# 33333.net
KiCad netlist of a schematic drawn in EasyEDA Pro
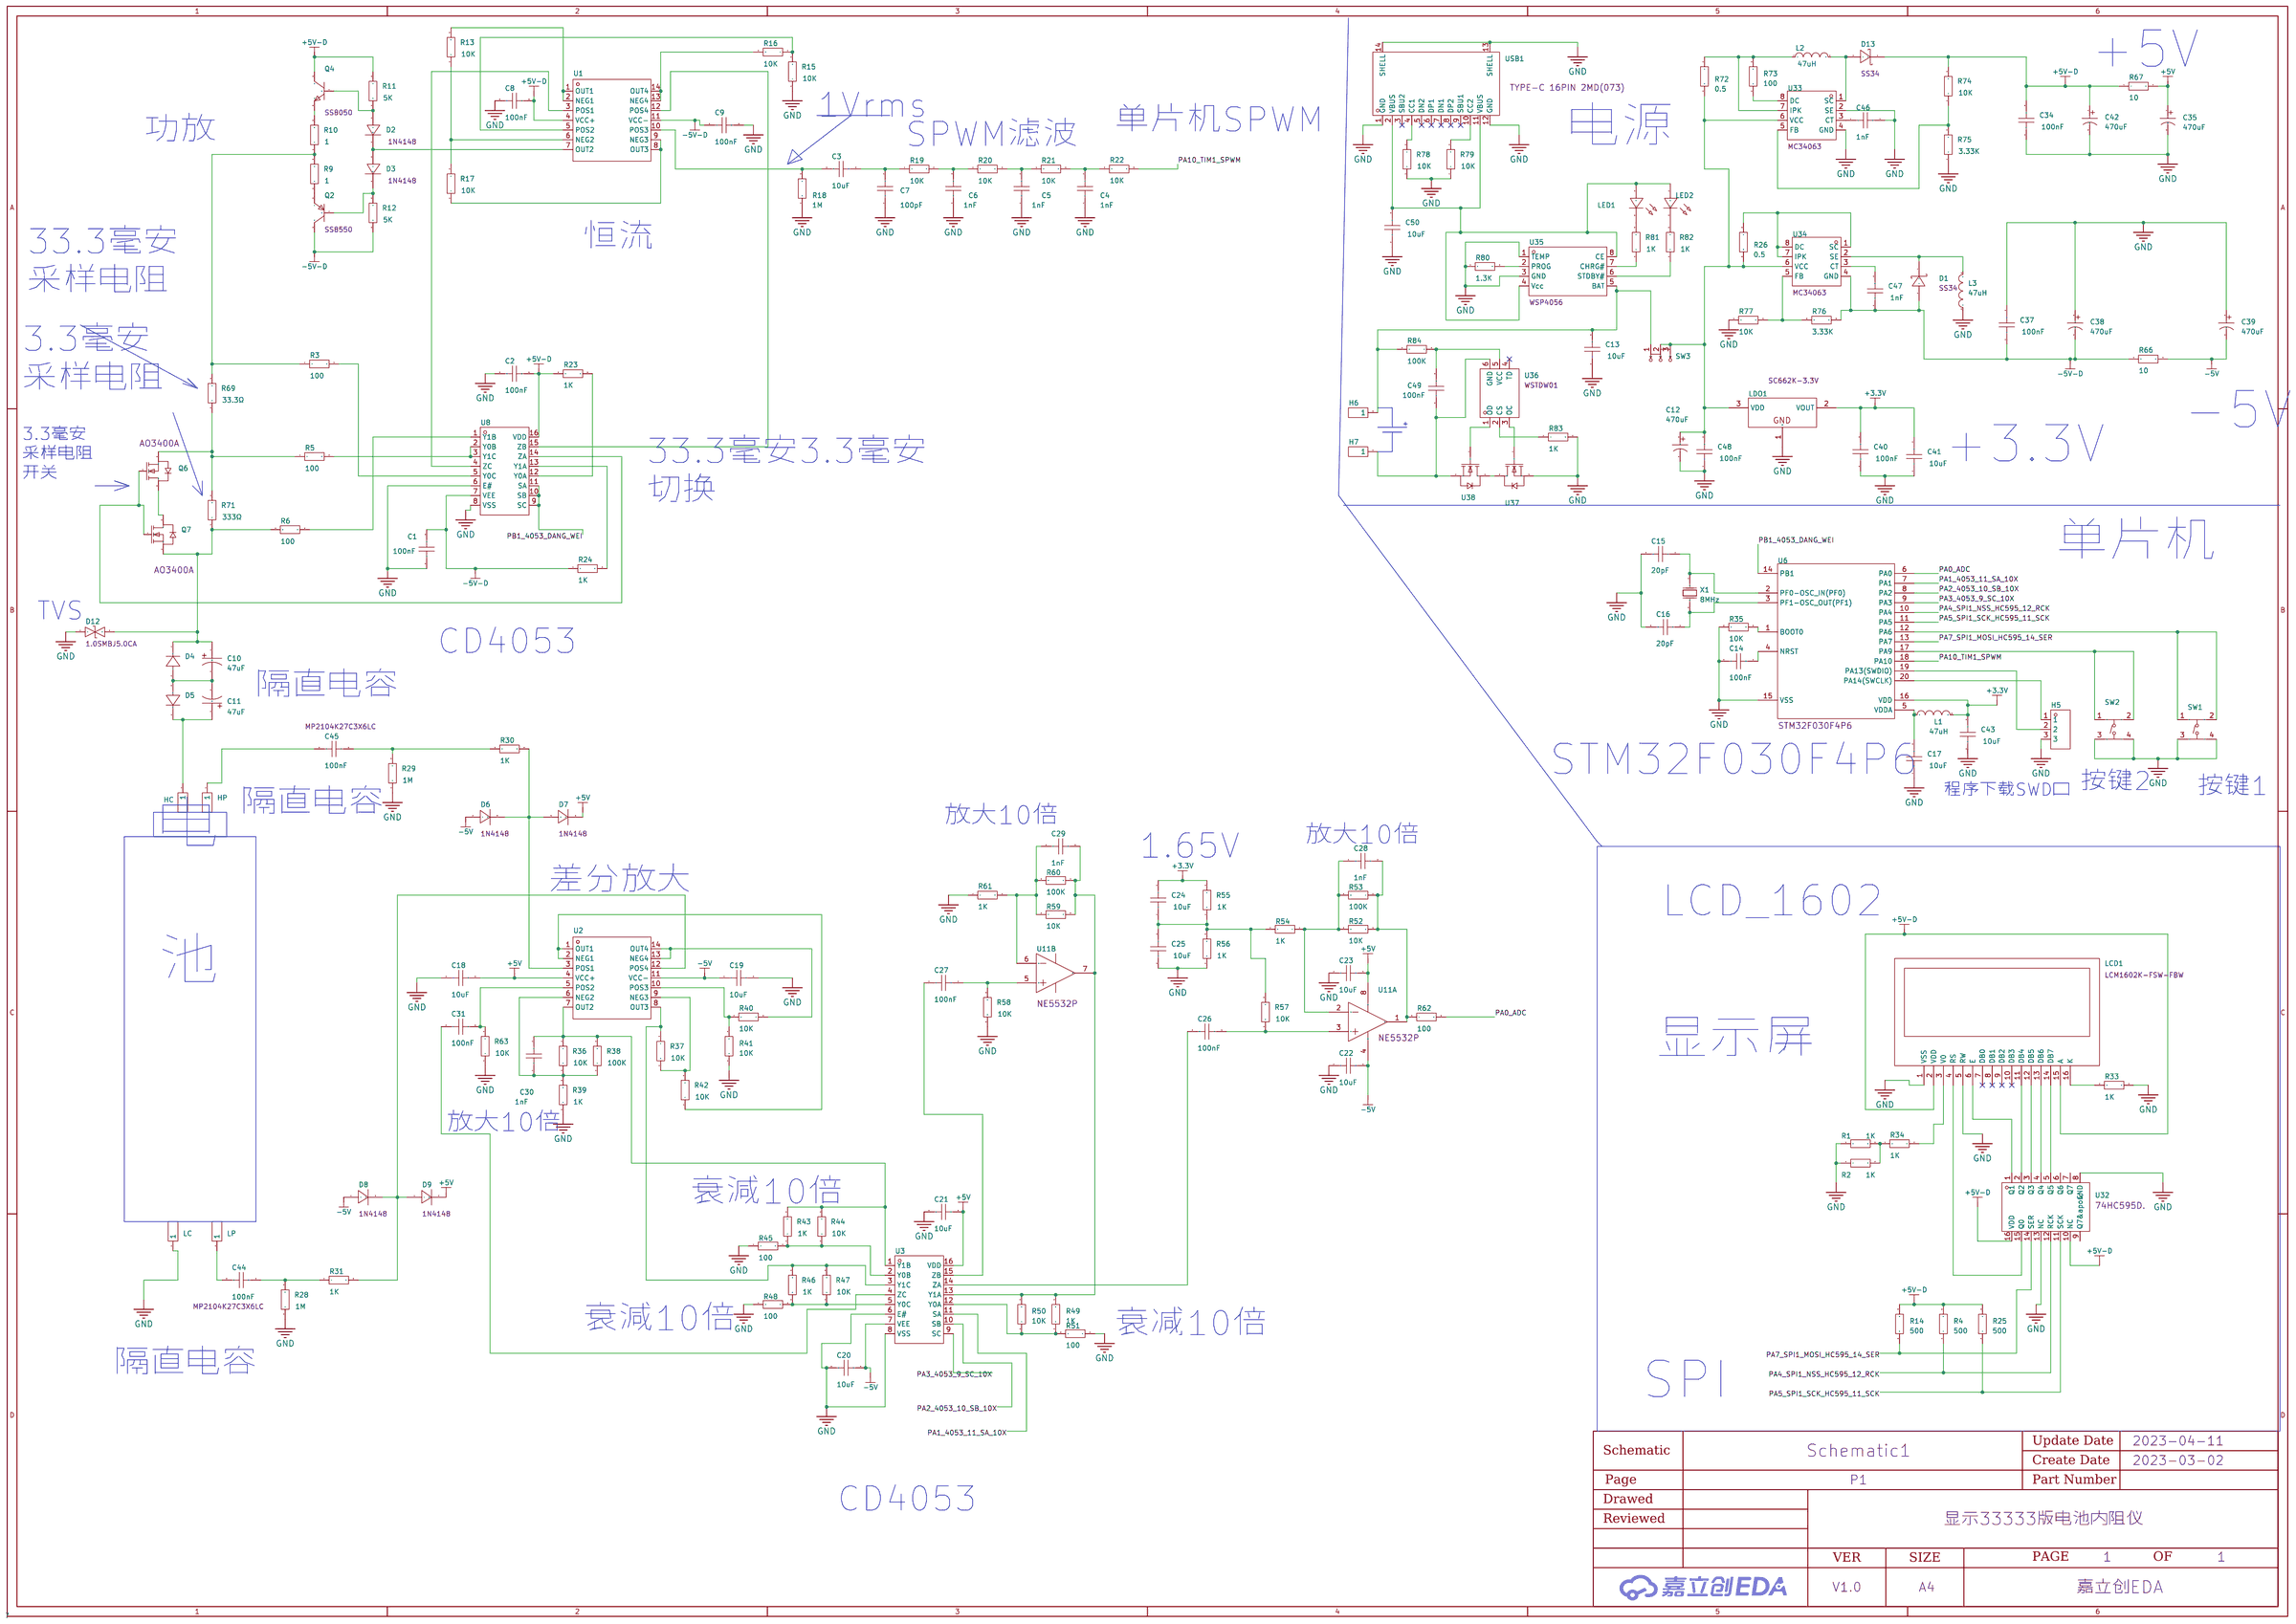
[diagram p0: schematic sheet]

(export (version "E")
  (design (tool "Eeschema 10.0.6"))
  (components
    (comp (ref "C1")
      (value "100nF")
      (footprint "easyedapro:C0603")
      (libsource (lib "easyedapro") (part "CapAcitance"))
    )
    (comp (ref "C2")
      (value "100nF")
      (footprint "easyedapro:C0603")
      (libsource (lib "easyedapro") (part "CapAcitance"))
    )
    (comp (ref "C3")
      (value "10uF")
      (footprint "easyedapro:C0603")
      (libsource (lib "easyedapro") (part "CapAcitance"))
    )
    (comp (ref "C4")
      (value "1nF")
      (footprint "easyedapro:C0603")
      (libsource (lib "easyedapro") (part "CapAcitance"))
    )
    (comp (ref "C5")
      (value "1nF")
      (footprint "easyedapro:C0603")
      (libsource (lib "easyedapro") (part "CapAcitance"))
    )
    (comp (ref "C6")
      (value "1nF")
      (footprint "easyedapro:C0603")
      (libsource (lib "easyedapro") (part "CapAcitance"))
    )
    (comp (ref "C7")
      (value "100pF")
      (footprint "easyedapro:C0603")
      (libsource (lib "easyedapro") (part "CapAcitance"))
    )
    (comp (ref "C8")
      (value "100nF")
      (footprint "easyedapro:C0603")
      (libsource (lib "easyedapro") (part "CapAcitance"))
    )
    (comp (ref "C9")
      (value "100nF")
      (footprint "easyedapro:C0603")
      (libsource (lib "easyedapro") (part "CapAcitance"))
    )
    (comp (ref "C10")
      (value "47uF")
      (footprint "easyedapro:CAP-TH_BD10.0-P5.00-D1.0-FD")
      (description "容值:47uF;精度:±20%;额定电压:200V;电容体直径:10mm;电容体长度:20mm;脚间距:5mm;工作寿命:5000hrs@105℃;")
      (fields (field (name "Manufacturer Part") "KF470M200G200A") (field (name "Manufacturer") "CapXon(丰宾)"))
      (libsource (lib "easyedapro") (part "KF470M200G200A"))
    )
    (comp (ref "C11")
      (value "47uF")
      (footprint "easyedapro:CAP-TH_BD10.0-P5.00-D1.0-FD")
      (description "容值:47uF;精度:±20%;额定电压:200V;电容体直径:10mm;电容体长度:20mm;脚间距:5mm;工作寿命:5000hrs@105℃;")
      (fields (field (name "Manufacturer Part") "KF470M200G200A") (field (name "Manufacturer") "CapXon(丰宾)"))
      (libsource (lib "easyedapro") (part "KF470M200G200A"))
    )
    (comp (ref "C12")
      (value "470uF")
      (footprint "easyedapro:CAP-TH_BD8.0-P3.50-D0.6-FD")
      (description "容值:470uF;精度:±20%;额定电压:16V;电容体直径:8mm;电容体长度:12mm;脚间距:3.5mm;工作寿命:2000hrs@105℃;")
      (fields
        (field (name "Manufacturer Part") "KM477M016F12RR0VH2FP0")
        (field (name "Manufacturer") "CX(承兴)")
      )
      (libsource (lib "easyedapro") (part "470uf16v"))
    )
    (comp (ref "C13")
      (value "10uF")
      (footprint "easyedapro:C0603")
      (libsource (lib "easyedapro") (part "CapAcitance"))
    )
    (comp (ref "C14")
      (value "100nF")
      (footprint "easyedapro:C0603")
      (libsource (lib "easyedapro") (part "CapAcitance"))
    )
    (comp (ref "C15")
      (value "20pF")
      (footprint "easyedapro:C0603")
      (libsource (lib "easyedapro") (part "CapAcitance"))
    )
    (comp (ref "C16")
      (value "20pF")
      (footprint "easyedapro:C0603")
      (libsource (lib "easyedapro") (part "CapAcitance"))
    )
    (comp (ref "C17")
      (value "10uF")
      (footprint "easyedapro:C0603")
      (libsource (lib "easyedapro") (part "CapAcitance"))
    )
    (comp (ref "C18")
      (value "10uF")
      (footprint "easyedapro:C0603")
      (libsource (lib "easyedapro") (part "CapAcitance"))
    )
    (comp (ref "C19")
      (value "10uF")
      (footprint "easyedapro:C0603")
      (libsource (lib "easyedapro") (part "CapAcitance"))
    )
    (comp (ref "C20")
      (value "10uF")
      (footprint "easyedapro:C0603")
      (libsource (lib "easyedapro") (part "CapAcitance"))
    )
    (comp (ref "C21")
      (value "10uF")
      (footprint "easyedapro:C0603")
      (libsource (lib "easyedapro") (part "CapAcitance"))
    )
    (comp (ref "C22")
      (value "10uF")
      (footprint "easyedapro:C0603")
      (libsource (lib "easyedapro") (part "CapAcitance"))
    )
    (comp (ref "C23")
      (value "10uF")
      (footprint "easyedapro:C0603")
      (libsource (lib "easyedapro") (part "CapAcitance"))
    )
    (comp (ref "C24")
      (value "10uF")
      (footprint "easyedapro:C0603")
      (libsource (lib "easyedapro") (part "CapAcitance"))
    )
    (comp (ref "C25")
      (value "10uF")
      (footprint "easyedapro:C0603")
      (libsource (lib "easyedapro") (part "CapAcitance"))
    )
    (comp (ref "C26")
      (value "100nF")
      (footprint "easyedapro:C0603")
      (libsource (lib "easyedapro") (part "CapAcitance"))
    )
    (comp (ref "C27")
      (value "100nF")
      (footprint "easyedapro:C0603")
      (libsource (lib "easyedapro") (part "CapAcitance"))
    )
    (comp (ref "C28")
      (value "1nF")
      (footprint "easyedapro:C0603")
      (libsource (lib "easyedapro") (part "CapAcitance"))
    )
    (comp (ref "C29")
      (value "1nF")
      (footprint "easyedapro:C0603")
      (libsource (lib "easyedapro") (part "CapAcitance"))
    )
    (comp (ref "C30")
      (value "1nF")
      (footprint "easyedapro:C0603")
      (libsource (lib "easyedapro") (part "CapAcitance"))
    )
    (comp (ref "C31")
      (value "100nF")
      (footprint "easyedapro:C0603")
      (libsource (lib "easyedapro") (part "CapAcitance"))
    )
    (comp (ref "C34")
      (value "100nF")
      (footprint "easyedapro:C0603")
      (libsource (lib "easyedapro") (part "CapAcitance"))
    )
    (comp (ref "C35")
      (value "470uF")
      (footprint "easyedapro:CAP-TH_BD8.0-P3.50-D0.6-FD")
      (description "容值:470uF;精度:±20%;额定电压:16V;电容体直径:8mm;电容体长度:12mm;脚间距:3.5mm;工作寿命:2000hrs@105℃;")
      (fields
        (field (name "Manufacturer Part") "KM477M016F12RR0VH2FP0")
        (field (name "Manufacturer") "CX(承兴)")
      )
      (libsource (lib "easyedapro") (part "470uf16v"))
    )
    (comp (ref "C37")
      (value "100nF")
      (footprint "easyedapro:C0603")
      (libsource (lib "easyedapro") (part "CapAcitance"))
    )
    (comp (ref "C38")
      (value "470uF")
      (footprint "easyedapro:CAP-TH_BD8.0-P3.50-D0.6-FD")
      (description "容值:470uF;精度:±20%;额定电压:16V;电容体直径:8mm;电容体长度:12mm;脚间距:3.5mm;工作寿命:2000hrs@105℃;")
      (fields
        (field (name "Manufacturer Part") "KM477M016F12RR0VH2FP0")
        (field (name "Manufacturer") "CX(承兴)")
      )
      (libsource (lib "easyedapro") (part "470uf16v"))
    )
    (comp (ref "C39")
      (value "470uF")
      (footprint "easyedapro:CAP-TH_BD8.0-P3.50-D0.6-FD")
      (description "容值:470uF;精度:±20%;额定电压:16V;电容体直径:8mm;电容体长度:12mm;脚间距:3.5mm;工作寿命:2000hrs@105℃;")
      (fields
        (field (name "Manufacturer Part") "KM477M016F12RR0VH2FP0")
        (field (name "Manufacturer") "CX(承兴)")
      )
      (libsource (lib "easyedapro") (part "470uf16v"))
    )
    (comp (ref "C40")
      (value "100nF")
      (footprint "easyedapro:C0603")
      (libsource (lib "easyedapro") (part "CapAcitance"))
    )
    (comp (ref "C41")
      (value "10uF")
      (footprint "easyedapro:C0603")
      (libsource (lib "easyedapro") (part "CapAcitance"))
    )
    (comp (ref "C42")
      (value "470uF")
      (footprint "easyedapro:CAP-TH_BD8.0-P3.50-D0.6-FD")
      (description "容值:470uF;精度:±20%;额定电压:16V;电容体直径:8mm;电容体长度:12mm;脚间距:3.5mm;工作寿命:2000hrs@105℃;")
      (fields
        (field (name "Manufacturer Part") "KM477M016F12RR0VH2FP0")
        (field (name "Manufacturer") "CX(承兴)")
      )
      (libsource (lib "easyedapro") (part "470uf16v"))
    )
    (comp (ref "C43")
      (value "10uF")
      (footprint "easyedapro:C0603")
      (libsource (lib "easyedapro") (part "CapAcitance"))
    )
    (comp (ref "C44")
      (value "100nF")
      (footprint "easyedapro:CAP-TH_L13.0-W6.0-P10.00-D1.0")
      (description "等级:X2;容值:100nF;精度:±10%;")
      (fields (field (name "Manufacturer Part") "MP2104K27C3X6LC") (field (name "Manufacturer") "SRD(圣融达)"))
      (libsource (lib "easyedapro") (part "MP2104KGC3XLC"))
    )
    (comp (ref "C45")
      (value "100nF")
      (footprint "easyedapro:CAP-TH_L13.0-W6.0-P10.00-D1.0")
      (description "等级:X2;容值:100nF;精度:±10%;")
      (fields (field (name "Manufacturer Part") "MP2104K27C3X6LC") (field (name "Manufacturer") "SRD(圣融达)"))
      (libsource (lib "easyedapro") (part "MP2104KGC3XLC"))
    )
    (comp (ref "C46")
      (value "1nF")
      (footprint "easyedapro:C0603")
      (libsource (lib "easyedapro") (part "CapAcitance"))
    )
    (comp (ref "C47")
      (value "1nF")
      (footprint "easyedapro:C0603")
      (libsource (lib "easyedapro") (part "CapAcitance"))
    )
    (comp (ref "C48")
      (value "100nF")
      (footprint "easyedapro:C0603")
      (libsource (lib "easyedapro") (part "CapAcitance"))
    )
    (comp (ref "C49")
      (value "100nF")
      (footprint "easyedapro:C0603")
      (libsource (lib "easyedapro") (part "CapAcitance"))
    )
    (comp (ref "C50")
      (value "10uF")
      (footprint "easyedapro:C0603")
      (libsource (lib "easyedapro") (part "CapAcitance"))
    )
    (comp (ref "D1")
      (value "SS34")
      (footprint "easyedapro:SMA_L4.3-W2.6-LS5.2-RD")
      (description "二极管配置:独立式;直流反向耐压(Vr):40V;平均整流电流(Io):3A;正向压降(Vf):550mV@3A;反向电流(Ir):500uA@40V;")
      (fields (field (name "Manufacturer Part") "SS34") (field (name "Manufacturer") "MDD"))
      (libsource (lib "easyedapro") (part "SS34_C8678"))
    )
    (comp (ref "D2")
      (value "1N4148")
      (footprint "easyedapro:DO-35_BD2.0-L4.0-P8.00-D0.5-FD")
      (fields (field (name "Manufacturer Part") "1N4148") (field (name "Manufacturer") "ST(先科)"))
      (libsource (lib "easyedapro") (part "1N4148"))
    )
    (comp (ref "D3")
      (value "1N4148")
      (footprint "easyedapro:DO-35_BD2.0-L4.0-P8.00-D0.5-FD")
      (fields (field (name "Manufacturer Part") "1N4148") (field (name "Manufacturer") "ST(先科)"))
      (libsource (lib "easyedapro") (part "1N4148"))
    )
    (comp (ref "D4")
      (value "~")
      (footprint "easyedapro:DO_1N4007")
      (libsource (lib "easyedapro") (part "D_1N4007"))
    )
    (comp (ref "D5")
      (value "~")
      (footprint "easyedapro:DO_1N4007")
      (libsource (lib "easyedapro") (part "D_1N4007"))
    )
    (comp (ref "D6")
      (value "1N4148")
      (footprint "easyedapro:DO-35_BD2.0-L4.0-P8.00-D0.5-FD")
      (fields (field (name "Manufacturer Part") "1N4148") (field (name "Manufacturer") "ST(先科)"))
      (libsource (lib "easyedapro") (part "1N4148"))
    )
    (comp (ref "D7")
      (value "1N4148")
      (footprint "easyedapro:DO-35_BD2.0-L4.0-P8.00-D0.5-FD")
      (fields (field (name "Manufacturer Part") "1N4148") (field (name "Manufacturer") "ST(先科)"))
      (libsource (lib "easyedapro") (part "1N4148"))
    )
    (comp (ref "D8")
      (value "1N4148")
      (footprint "easyedapro:DO-35_BD2.0-L4.0-P8.00-D0.5-FD")
      (fields (field (name "Manufacturer Part") "1N4148") (field (name "Manufacturer") "ST(先科)"))
      (libsource (lib "easyedapro") (part "1N4148"))
    )
    (comp (ref "D9")
      (value "1N4148")
      (footprint "easyedapro:DO-35_BD2.0-L4.0-P8.00-D0.5-FD")
      (fields (field (name "Manufacturer Part") "1N4148") (field (name "Manufacturer") "ST(先科)"))
      (libsource (lib "easyedapro") (part "1N4148"))
    )
    (comp (ref "D12")
      (value "1.0SMBJ5.0CA")
      (footprint "easyedapro:SMB_L4.6-W3.6-LS5.3-BI")
      (description "极性:双向;反向截止电压(Vrwm):5V;击穿电压:6.4V;峰值脉冲电流(Ipp)@10/1000s:108.7A;最大钳位电压:9.2V;")
      (fields (field (name "Manufacturer Part") "1.0SMBJ5.0CA") (field (name "Manufacturer") "BORN(伯恩半导体)"))
      (libsource (lib "easyedapro") (part "1.0SMBJ5.0CA"))
    )
    (comp (ref "D13")
      (value "SS34")
      (footprint "easyedapro:SMA_L4.3-W2.6-LS5.2-RD")
      (description "二极管配置:独立式;直流反向耐压(Vr):40V;平均整流电流(Io):3A;正向压降(Vf):550mV@3A;反向电流(Ir):500uA@40V;")
      (fields (field (name "Manufacturer Part") "SS34") (field (name "Manufacturer") "MDD"))
      (libsource (lib "easyedapro") (part "SS34_C8678"))
    )
    (comp (ref "H5")
      (value "~")
      (footprint "easyedapro:HDR-TH_3P-P2.54-V-M")
      (libsource (lib "easyedapro") (part "PZ254V-11-03P_C2937625"))
    )
    (comp (ref "H6")
      (value "~")
      (footprint "easyedapro:HDR-TH_1P-V-M_XKB_X4611WV-01I-C28D40")
      (libsource (lib "easyedapro") (part "HDR_1x1"))
    )
    (comp (ref "H7")
      (value "~")
      (footprint "easyedapro:HDR-TH_1P-V-M_XKB_X4611WV-01I-C28D40")
      (libsource (lib "easyedapro") (part "HDR_1x1"))
    )
    (comp (ref "HC")
      (value "~")
      (footprint "easyedapro:HDR-TH_1P-V-M_XKB_X4611WV-01I-C28D40")
      (libsource (lib "easyedapro") (part "HDR_1x1"))
    )
    (comp (ref "HP")
      (value "~")
      (footprint "easyedapro:HDR-TH_1P-V-M_XKB_X4611WV-01I-C28D40")
      (libsource (lib "easyedapro") (part "HDR_1x1"))
    )
    (comp (ref "L1")
      (value "47uH")
      (footprint "easyedapro:IND-SMD_L4.5-W4.0_SLF0403")
      (description "电感值:47uH;直流电阻(DCR):844mΩ;精度:±10%;额定电流:540mA;")
      (fields
        (field (name "Manufacturer Part") "SLF0403-470KTT")
        (field (name "Manufacturer") "Sunltech(韩国顺磁)")
      )
      (libsource (lib "easyedapro") (part "SLF0403-470KTT"))
    )
    (comp (ref "L2")
      (value "47uH")
      (footprint "easyedapro:IND-SMD_L4.5-W4.0_SLF0403")
      (description "电感值:47uH;直流电阻(DCR):844mΩ;精度:±10%;额定电流:540mA;")
      (fields
        (field (name "Manufacturer Part") "SLF0403-470KTT")
        (field (name "Manufacturer") "Sunltech(韩国顺磁)")
      )
      (libsource (lib "easyedapro") (part "SLF0403-470KTT"))
    )
    (comp (ref "L3")
      (value "47uH")
      (footprint "easyedapro:IND-SMD_L4.5-W4.0_SLF0403")
      (description "电感值:47uH;直流电阻(DCR):844mΩ;精度:±10%;额定电流:540mA;")
      (fields
        (field (name "Manufacturer Part") "SLF0403-470KTT")
        (field (name "Manufacturer") "Sunltech(韩国顺磁)")
      )
      (libsource (lib "easyedapro") (part "SLF0403-470KTT"))
    )
    (comp (ref "LC")
      (value "~")
      (footprint "easyedapro:HDR-TH_1P-V-M_XKB_X4611WV-01I-C28D40")
      (libsource (lib "easyedapro") (part "HDR_1x1"))
    )
    (comp (ref "LCD1")
      (value "LCM1602K-FSW-FBW")
      (footprint "easyedapro:MODULE-TH_LCM1602K")
      (description "尺寸(inch):-;主控芯片:KS0066U;")
      (fields
        (field (name "Manufacturer Part") "LCM1602K-FSW-FBW")
        (field (name "Manufacturer") "LONTECH(厦门龙特)")
      )
      (libsource (lib "easyedapro") (part "LCM1602K-FSW-FBW"))
    )
    (comp (ref "LDO1")
      (value "SC662K-3.3V")
      (footprint "easyedapro:SOT-23-3_L2.9-W1.3-P1.90-LS2.4-BR")
      (description "输出类型:固定;输出极性:正;最大输入电压:6V;输出电压:3.3V;输出电流:250mA;电源纹波抑制比(PSRR):50dB@(1kHz);")
      (fields (field (name "Manufacturer Part") "SC662K-3.3V") (field (name "Manufacturer") "FM(富满)"))
      (libsource (lib "easyedapro") (part "SC662K-3.3V"))
    )
    (comp (ref "LED1")
      (value "~")
      (footprint "easyedapro:LED_TH-3mm")
      (libsource (lib "easyedapro") (part "LED_TH-R"))
    )
    (comp (ref "LED2")
      (value "~")
      (footprint "easyedapro:LED_TH-3mm")
      (libsource (lib "easyedapro") (part "LED_TH-R"))
    )
    (comp (ref "LP")
      (value "~")
      (footprint "easyedapro:HDR-TH_1P-V-M_XKB_X4611WV-01I-C28D40")
      (libsource (lib "easyedapro") (part "HDR_1x1"))
    )
    (comp (ref "Q2")
      (value "SS8550")
      (footprint "easyedapro:SOT-23-3_L2.9-W1.6-P1.90-LS2.8-BR")
      (fields (field (name "Manufacturer Part") "SS8550") (field (name "Manufacturer") "ElecSuper(静芯微）"))
      (libsource (lib "easyedapro") (part "SS8550_C5249677"))
    )
    (comp (ref "Q4")
      (value "SS8050")
      (footprint "easyedapro:SOT-23-3_L2.9-W1.6-P1.90-LS2.8-BR")
      (fields (field (name "Manufacturer Part") "SS8050") (field (name "Manufacturer") "ElecSuper(静芯微）"))
      (libsource (lib "easyedapro") (part "SS8050_C5249676"))
    )
    (comp (ref "Q6")
      (value "AO3400A")
      (footprint "easyedapro:SOT-23-3_L2.9-W1.3-P1.90-LS2.4-BR")
      (fields (field (name "Manufacturer Part") "AO3400A") (field (name "Manufacturer") "UMW(广东友台半导体)"))
      (libsource (lib "easyedapro") (part "AO3400A_C347475"))
    )
    (comp (ref "Q7")
      (value "AO3400A")
      (footprint "easyedapro:SOT-23-3_L2.9-W1.3-P1.90-LS2.4-BR")
      (fields (field (name "Manufacturer Part") "AO3400A") (field (name "Manufacturer") "UMW(广东友台半导体)"))
      (libsource (lib "easyedapro") (part "AO3400A_C347475"))
    )
    (comp (ref "R1")
      (value "1K")
      (footprint "easyedapro:Res_1/8W")
      (libsource (lib "easyedapro") (part "电阻"))
    )
    (comp (ref "R2")
      (value "1K")
      (footprint "easyedapro:Res_1/8W")
      (libsource (lib "easyedapro") (part "电阻"))
    )
    (comp (ref "R3")
      (value "100")
      (footprint "easyedapro:Res_1/8W")
      (libsource (lib "easyedapro") (part "电阻"))
    )
    (comp (ref "R4")
      (value "500")
      (footprint "easyedapro:Res_1/8W")
      (libsource (lib "easyedapro") (part "电阻"))
    )
    (comp (ref "R5")
      (value "100")
      (footprint "easyedapro:Res_1/8W")
      (libsource (lib "easyedapro") (part "电阻"))
    )
    (comp (ref "R6")
      (value "100")
      (footprint "easyedapro:Res_1/8W")
      (libsource (lib "easyedapro") (part "电阻"))
    )
    (comp (ref "R9") (value "1") (footprint "easyedapro:Res_1/8W") (libsource (lib "easyedapro") (part "电阻")))
    (comp (ref "R10")
      (value "1")
      (footprint "easyedapro:Res_1/8W")
      (libsource (lib "easyedapro") (part "电阻"))
    )
    (comp (ref "R11")
      (value "5K")
      (footprint "easyedapro:Res_1/8W")
      (libsource (lib "easyedapro") (part "电阻"))
    )
    (comp (ref "R12")
      (value "5K")
      (footprint "easyedapro:Res_1/8W")
      (libsource (lib "easyedapro") (part "电阻"))
    )
    (comp (ref "R13")
      (value "10K")
      (footprint "easyedapro:Res_1/8W")
      (libsource (lib "easyedapro") (part "电阻"))
    )
    (comp (ref "R14")
      (value "500")
      (footprint "easyedapro:Res_1/8W")
      (libsource (lib "easyedapro") (part "电阻"))
    )
    (comp (ref "R15")
      (value "10K")
      (footprint "easyedapro:Res_1/8W")
      (libsource (lib "easyedapro") (part "电阻"))
    )
    (comp (ref "R16")
      (value "10K")
      (footprint "easyedapro:Res_1/8W")
      (libsource (lib "easyedapro") (part "电阻"))
    )
    (comp (ref "R17")
      (value "10K")
      (footprint "easyedapro:Res_1/8W")
      (libsource (lib "easyedapro") (part "电阻"))
    )
    (comp (ref "R18")
      (value "1M")
      (footprint "easyedapro:Res_1/8W")
      (libsource (lib "easyedapro") (part "电阻"))
    )
    (comp (ref "R19")
      (value "10K")
      (footprint "easyedapro:Res_1/8W")
      (libsource (lib "easyedapro") (part "电阻"))
    )
    (comp (ref "R20")
      (value "10K")
      (footprint "easyedapro:Res_1/8W")
      (libsource (lib "easyedapro") (part "电阻"))
    )
    (comp (ref "R21")
      (value "10K")
      (footprint "easyedapro:Res_1/8W")
      (libsource (lib "easyedapro") (part "电阻"))
    )
    (comp (ref "R22")
      (value "10K")
      (footprint "easyedapro:Res_1/8W")
      (libsource (lib "easyedapro") (part "电阻"))
    )
    (comp (ref "R23")
      (value "1K")
      (footprint "easyedapro:Res_1/8W")
      (libsource (lib "easyedapro") (part "电阻"))
    )
    (comp (ref "R24")
      (value "1K")
      (footprint "easyedapro:Res_1/8W")
      (libsource (lib "easyedapro") (part "电阻"))
    )
    (comp (ref "R25")
      (value "500")
      (footprint "easyedapro:Res_1/8W")
      (libsource (lib "easyedapro") (part "电阻"))
    )
    (comp (ref "R26") (value "0.5") (footprint "easyedapro:R0603") (libsource (lib "easyedapro") (part "电阻")))
    (comp (ref "R28")
      (value "1M")
      (footprint "easyedapro:Res_1/8W")
      (libsource (lib "easyedapro") (part "电阻"))
    )
    (comp (ref "R29")
      (value "1M")
      (footprint "easyedapro:Res_1/8W")
      (libsource (lib "easyedapro") (part "电阻"))
    )
    (comp (ref "R30")
      (value "1K")
      (footprint "easyedapro:Res_1/8W")
      (libsource (lib "easyedapro") (part "电阻"))
    )
    (comp (ref "R31")
      (value "1K")
      (footprint "easyedapro:Res_1/8W")
      (libsource (lib "easyedapro") (part "电阻"))
    )
    (comp (ref "R33")
      (value "1K")
      (footprint "easyedapro:Res_1/8W")
      (libsource (lib "easyedapro") (part "电阻"))
    )
    (comp (ref "R34")
      (value "1K")
      (footprint "easyedapro:Res_1/8W")
      (libsource (lib "easyedapro") (part "电阻"))
    )
    (comp (ref "R35")
      (value "10K")
      (footprint "easyedapro:Res_1/8W")
      (libsource (lib "easyedapro") (part "电阻"))
    )
    (comp (ref "R36")
      (value "10K")
      (footprint "easyedapro:Res_1/8W")
      (libsource (lib "easyedapro") (part "电阻"))
    )
    (comp (ref "R37")
      (value "10K")
      (footprint "easyedapro:Res_1/8W")
      (libsource (lib "easyedapro") (part "电阻"))
    )
    (comp (ref "R38")
      (value "100K")
      (footprint "easyedapro:Res_1/8W")
      (libsource (lib "easyedapro") (part "电阻"))
    )
    (comp (ref "R39")
      (value "1K")
      (footprint "easyedapro:Res_1/8W")
      (libsource (lib "easyedapro") (part "电阻"))
    )
    (comp (ref "R40")
      (value "10K")
      (footprint "easyedapro:Res_1/8W")
      (libsource (lib "easyedapro") (part "电阻"))
    )
    (comp (ref "R41")
      (value "10K")
      (footprint "easyedapro:Res_1/8W")
      (libsource (lib "easyedapro") (part "电阻"))
    )
    (comp (ref "R42")
      (value "10K")
      (footprint "easyedapro:Res_1/8W")
      (libsource (lib "easyedapro") (part "电阻"))
    )
    (comp (ref "R43")
      (value "1K")
      (footprint "easyedapro:Res_1/8W")
      (libsource (lib "easyedapro") (part "电阻"))
    )
    (comp (ref "R44")
      (value "10K")
      (footprint "easyedapro:Res_1/8W")
      (libsource (lib "easyedapro") (part "电阻"))
    )
    (comp (ref "R45")
      (value "100")
      (footprint "easyedapro:Res_1/8W")
      (libsource (lib "easyedapro") (part "电阻"))
    )
    (comp (ref "R46")
      (value "1K")
      (footprint "easyedapro:Res_1/8W")
      (libsource (lib "easyedapro") (part "电阻"))
    )
    (comp (ref "R47")
      (value "10K")
      (footprint "easyedapro:Res_1/8W")
      (libsource (lib "easyedapro") (part "电阻"))
    )
    (comp (ref "R48")
      (value "100")
      (footprint "easyedapro:Res_1/8W")
      (libsource (lib "easyedapro") (part "电阻"))
    )
    (comp (ref "R49")
      (value "1K")
      (footprint "easyedapro:Res_1/8W")
      (libsource (lib "easyedapro") (part "电阻"))
    )
    (comp (ref "R50")
      (value "10K")
      (footprint "easyedapro:Res_1/8W")
      (libsource (lib "easyedapro") (part "电阻"))
    )
    (comp (ref "R51")
      (value "100")
      (footprint "easyedapro:Res_1/8W")
      (libsource (lib "easyedapro") (part "电阻"))
    )
    (comp (ref "R52")
      (value "10K")
      (footprint "easyedapro:Res_1/8W")
      (libsource (lib "easyedapro") (part "电阻"))
    )
    (comp (ref "R53")
      (value "100K")
      (footprint "easyedapro:Res_1/8W")
      (libsource (lib "easyedapro") (part "电阻"))
    )
    (comp (ref "R54")
      (value "1K")
      (footprint "easyedapro:Res_1/8W")
      (libsource (lib "easyedapro") (part "电阻"))
    )
    (comp (ref "R55")
      (value "1K")
      (footprint "easyedapro:Res_1/8W")
      (libsource (lib "easyedapro") (part "电阻"))
    )
    (comp (ref "R56")
      (value "1K")
      (footprint "easyedapro:Res_1/8W")
      (libsource (lib "easyedapro") (part "电阻"))
    )
    (comp (ref "R57")
      (value "10K")
      (footprint "easyedapro:Res_1/8W")
      (libsource (lib "easyedapro") (part "电阻"))
    )
    (comp (ref "R58")
      (value "10K")
      (footprint "easyedapro:Res_1/8W")
      (libsource (lib "easyedapro") (part "电阻"))
    )
    (comp (ref "R59")
      (value "10K")
      (footprint "easyedapro:Res_1/8W")
      (libsource (lib "easyedapro") (part "电阻"))
    )
    (comp (ref "R60")
      (value "100K")
      (footprint "easyedapro:Res_1/8W")
      (libsource (lib "easyedapro") (part "电阻"))
    )
    (comp (ref "R61")
      (value "1K")
      (footprint "easyedapro:Res_1/8W")
      (libsource (lib "easyedapro") (part "电阻"))
    )
    (comp (ref "R62")
      (value "100")
      (footprint "easyedapro:Res_1/8W")
      (libsource (lib "easyedapro") (part "电阻"))
    )
    (comp (ref "R63")
      (value "10K")
      (footprint "easyedapro:Res_1/8W")
      (libsource (lib "easyedapro") (part "电阻"))
    )
    (comp (ref "R66") (value "10") (footprint "easyedapro:R0603") (libsource (lib "easyedapro") (part "电阻")))
    (comp (ref "R67") (value "10") (footprint "easyedapro:R0603") (libsource (lib "easyedapro") (part "电阻")))
    (comp (ref "R69")
      (value "33.3Ω")
      (footprint "easyedapro:R2512")
      (description "电阻类型:厚膜电阻;阻值:10Ω;精度:±5%;功率:2W;温度系数:±200ppm/℃;最大工作电压:200V;工作温度范围:-55℃~+155℃;")
      (fields (field (name "Manufacturer Part") "RC2512JK-7W10RL") (field (name "Manufacturer") "YAGEO(国巨)"))
      (libsource (lib "easyedapro") (part "RC2512JK-7W10RL"))
    )
    (comp (ref "R71")
      (value "333Ω")
      (footprint "easyedapro:R0603")
      (description "电阻类型:厚膜电阻;阻值:100Ω;精度:±1%;功率:100mW;温度系数:±100ppm/℃;最大工作电压:75V;工作温度范围:-55℃~+155℃;")
      (fields (field (name "Manufacturer Part") "AC0603FR-07100RL") (field (name "Manufacturer") "YAGEO(国巨)"))
      (libsource (lib "easyedapro") (part "AC0603FR-07100RL"))
    )
    (comp (ref "R72") (value "0.5") (footprint "easyedapro:R0603") (libsource (lib "easyedapro") (part "电阻")))
    (comp (ref "R73") (value "100") (footprint "easyedapro:R0603") (libsource (lib "easyedapro") (part "电阻")))
    (comp (ref "R74") (value "10K") (footprint "easyedapro:R0603") (libsource (lib "easyedapro") (part "电阻")))
    (comp (ref "R75")
      (value "3.33K")
      (footprint "easyedapro:R0603")
      (libsource (lib "easyedapro") (part "电阻"))
    )
    (comp (ref "R76")
      (value "3.33K")
      (footprint "easyedapro:R0603")
      (libsource (lib "easyedapro") (part "电阻"))
    )
    (comp (ref "R77") (value "10K") (footprint "easyedapro:R0603") (libsource (lib "easyedapro") (part "电阻")))
    (comp (ref "R78") (value "10K") (footprint "easyedapro:R0603") (libsource (lib "easyedapro") (part "电阻")))
    (comp (ref "R79") (value "10K") (footprint "easyedapro:R0603") (libsource (lib "easyedapro") (part "电阻")))
    (comp (ref "R80")
      (value "1.3K")
      (footprint "easyedapro:R0603")
      (libsource (lib "easyedapro") (part "电阻"))
    )
    (comp (ref "R81") (value "1K") (footprint "easyedapro:R0603") (libsource (lib "easyedapro") (part "电阻")))
    (comp (ref "R82") (value "1K") (footprint "easyedapro:R0603") (libsource (lib "easyedapro") (part "电阻")))
    (comp (ref "R83") (value "1K") (footprint "easyedapro:R0603") (libsource (lib "easyedapro") (part "电阻")))
    (comp (ref "R84")
      (value "100K")
      (footprint "easyedapro:R0603")
      (libsource (lib "easyedapro") (part "电阻"))
    )
    (comp (ref "SW1")
      (value "1TS005A-2600-5001")
      (footprint "easyedapro:SW-TH_4P-L6.0-W6.0-P4.50-LS6.5")
      (fields (field (name "Manufacturer") "HYP(鸿源精密)"))
      (libsource (lib "easyedapro") (part "1TS005A-2600-5001"))
    )
    (comp (ref "SW2")
      (value "1TS005A-2600-5001")
      (footprint "easyedapro:SW-TH_4P-L6.0-W6.0-P4.50-LS6.5")
      (fields (field (name "Manufacturer") "HYP(鸿源精密)"))
      (libsource (lib "easyedapro") (part "1TS005A-2600-5001"))
    )
    (comp (ref "SW3")
      (value "SS-12F20-G070")
      (footprint "easyedapro:SW-TH_G-SWITCH_SS-12F20-G070")
      (fields (field (name "Manufacturer") "G-Switch(品赞)"))
      (libsource (lib "easyedapro") (part "SS-12F20-G070"))
    )
    (comp (ref "U1")
      (value "TL084CN")
      (footprint "easyedapro:DIP-14_L17.8-W10.2-P2.54-BL")
      (description "运放类型:J-FET;放大器组数:4;增益带宽积（GBP）:4MHz;压摆率（SR）:16 V/us;电源电压:6V ~ 36V, ±3V ~ 18V;各通道供电电流:1.4mA;")
      (fields (field (name "Manufacturer") "TI(德州仪器)"))
      (libsource (lib "easyedapro") (part "TL084CN_C54501"))
    )
    (comp (ref "U2")
      (value "TL084CN")
      (footprint "easyedapro:DIP-14_L17.8-W10.2-P2.54-BL")
      (description "运放类型:J-FET;放大器组数:4;增益带宽积（GBP）:4MHz;压摆率（SR）:16 V/us;电源电压:6V ~ 36V, ±3V ~ 18V;各通道供电电流:1.4mA;")
      (fields (field (name "Manufacturer") "TI(德州仪器)"))
      (libsource (lib "easyedapro") (part "TL084CN_C54501"))
    )
    (comp (ref "U3")
      (value "CD4053BM/TR")
      (footprint "easyedapro:SOP-16_L9.9-W3.9-P1.27-LS6.1-BL")
      (fields (field (name "Manufacturer") "HGSEMI(华冠)"))
      (libsource (lib "easyedapro") (part "CD4053BM/TR"))
    )
    (comp (ref "U6")
      (value "STM32F030F4P6")
      (footprint "easyedapro:TSSOP-20_L6.5-W4.4-P0.65-LS6.4-BL")
      (fields (field (name "Manufacturer Part") "STM32F030F4P6") (field (name "Manufacturer") "ST(意法半导体)"))
      (libsource (lib "easyedapro") (part "STM32F030F4P6"))
    )
    (comp (ref "U8")
      (value "CD4053BM/TR")
      (footprint "easyedapro:SOP-16_L9.9-W3.9-P1.27-LS6.1-BL")
      (fields (field (name "Manufacturer") "HGSEMI(华冠)"))
      (libsource (lib "easyedapro") (part "CD4053BM/TR"))
    )
    (comp (ref "U11")
      (value "NE5532P")
      (footprint "easyedapro:DIP-8_L9.4-W6.4-P2.54-LS9.1-BL")
      (description "运放类型:General Purpose;放大器组数:2;增益带宽积（GBP）:10MHz;压摆率（SR）:9 V/us;电源电压:±5V ~ 15V;各通道供电电流:8mA;")
      (fields (field (name "Manufacturer Part") "NE5532P") (field (name "Manufacturer") "TI(德州仪器)"))
      (libsource (lib "easyedapro") (part "NE5532P"))
    )
    (comp (ref "U32")
      (value "74HC595D.")
      (footprint "easyedapro:SOP-16_L9.9-W3.9-P1.27-LS6.0-BL")
      (fields (field (name "Manufacturer Part") "74HC595D.") (field (name "Manufacturer") "FM(富满)"))
      (libsource (lib "easyedapro") (part "74HC595D."))
    )
    (comp (ref "U33")
      (value "MC34063")
      (footprint "easyedapro:SOIC-8_L5.0-W4.0-P1.27-LS6.0-BL")
      (fields (field (name "Manufacturer Part") "MC34063") (field (name "Manufacturer") "HXY MOSFET(华轩阳电子)"))
      (libsource (lib "easyedapro") (part "MC34063_C5349988"))
    )
    (comp (ref "U34")
      (value "MC34063")
      (footprint "easyedapro:SOIC-8_L5.0-W4.0-P1.27-LS6.0-BL")
      (fields (field (name "Manufacturer Part") "MC34063") (field (name "Manufacturer") "HXY MOSFET(华轩阳电子)"))
      (libsource (lib "easyedapro") (part "MC34063_C5349988"))
    )
    (comp (ref "U35")
      (value "WSP4056")
      (footprint "easyedapro:SOP-8_L5.1-W3.9-P1.27-LS6.0-BL")
      (fields (field (name "Manufacturer Part") "WSP4056") (field (name "Manufacturer") "WINSOK(微硕)"))
      (libsource (lib "easyedapro") (part "WSP4056"))
    )
    (comp (ref "U36")
      (value "WSTDW01")
      (footprint "easyedapro:SOT-23-6_L2.9-W1.6-P0.95-LS2.8-BR")
      (description "充电电池的类型:-;电池单元组数:-;最大充电电流:-;充满的电池组电压:-;最大供应电压:-;")
      (fields (field (name "Manufacturer Part") "WSTDW01") (field (name "Manufacturer") "WINSOK(微硕)"))
      (libsource (lib "easyedapro") (part "WSTDW01"))
    )
    (comp (ref "U37")
      (value "AO3400A")
      (footprint "easyedapro:SOT-23-3_L3.0-W1.6-P1.90-LS2.8-BR")
      (fields (field (name "Manufacturer") "ElecSuper(静芯微）"))
      (libsource (lib "easyedapro") (part "AO3400A_C5224194"))
    )
    (comp (ref "U38")
      (value "AO3400A")
      (footprint "easyedapro:SOT-23-3_L3.0-W1.6-P1.90-LS2.8-BR")
      (fields (field (name "Manufacturer") "ElecSuper(静芯微）"))
      (libsource (lib "easyedapro") (part "AO3400A_C5224194"))
    )
    (comp (ref "USB1")
      (value "TYPE-C 16PIN 2MD(073)")
      (footprint "easyedapro:USB-C-SMD_TYPE-C-6PIN-2MD-073")
      (description "连接器类型:Type-C;标准:-;公母:母座;触点数量:16;端口数量:1;安装方式:卧贴;额定电流 - 电源:5A;工作温度范围:-25℃~+85℃;")
      (fields
        (field (name "Manufacturer Part") "TYPE-C 16PIN 2MD(073)")
        (field (name "Manufacturer") "SHOU HAN(首韩)")
      )
      (libsource (lib "easyedapro") (part "TYPE-C 16PIN 2MD(073)"))
    )
    (comp (ref "X1")
      (value "8MHz")
      (footprint "easyedapro:OSC-TH_L10.0-W4.5-P5.00")
      (description "晶振类型:49S晶振;频率:8MHz;频率公差:±20ppm;频率稳定度:±30ppm;负载电容:20pF;工作温度:-20℃~+70℃;")
      (fields (field (name "Manufacturer Part") "X49SD8MSD2SC") (field (name "Manufacturer") "YXC(扬兴晶振)"))
      (libsource (lib "easyedapro") (part "X49SD8MSD2SC"))
    )
  )
  (nets
    (net (code "1") (name "+3.3V") (class "Default")
      (node (ref "C24") (pin "2") (pinfunction "2_2") (pintype "input"))
      (node (ref "C40") (pin "2") (pinfunction "2_2") (pintype "input"))
      (node (ref "C41") (pin "2") (pinfunction "2_2") (pintype "input"))
      (node (ref "C43") (pin "2") (pinfunction "2_2") (pintype "input"))
      (node (ref "L1") (pin "2") (pinfunction "2_2") (pintype "input"))
      (node (ref "LDO1") (pin "2") (pinfunction "VOUT_2") (pintype "input"))
      (node (ref "R55") (pin "2") (pinfunction "2_2") (pintype "input"))
      (node (ref "U6") (pin "16") (pinfunction "VDD_16") (pintype "input"))
    )
    (net (code "2") (name "+5V") (class "Default")
      (node (ref "C18") (pin "2") (pinfunction "2_2") (pintype "input"))
      (node (ref "C21") (pin "2") (pinfunction "2_2") (pintype "input"))
      (node (ref "C23") (pin "2") (pinfunction "2_2") (pintype "input"))
      (node (ref "C35") (pin "1") (pinfunction "1_1") (pintype "input"))
      (node (ref "D7") (pin "2") (pinfunction "C_2") (pintype "input"))
      (node (ref "D9") (pin "2") (pinfunction "C_2") (pintype "input"))
      (node (ref "R67") (pin "2") (pinfunction "2_2") (pintype "input"))
      (node (ref "U11") (pin "8") (pinfunction "VCC+_8") (pintype "input"))
      (node (ref "U2") (pin "4") (pinfunction "VCC+_4") (pintype "input"))
      (node (ref "U3") (pin "16") (pinfunction "VDD_16") (pintype "input"))
    )
    (net (code "3") (name "+5V-D") (class "Default")
      (node (ref "C2") (pin "2") (pinfunction "2_2") (pintype "input"))
      (node (ref "C34") (pin "2") (pinfunction "2_2") (pintype "input"))
      (node (ref "C42") (pin "1") (pinfunction "1_1") (pintype "input"))
      (node (ref "C8") (pin "2") (pinfunction "2_2") (pintype "input"))
      (node (ref "D13") (pin "1") (pinfunction "K_1") (pintype "input"))
      (node (ref "LCD1") (pin "15") (pinfunction "A_15") (pintype "input"))
      (node (ref "LCD1") (pin "2") (pinfunction "VDD_2") (pintype "input"))
      (node (ref "Q4") (pin "3") (pinfunction "C_3") (pintype "input"))
      (node (ref "R11") (pin "2") (pinfunction "2_2") (pintype "input"))
      (node (ref "R14") (pin "2") (pinfunction "2_2") (pintype "input"))
      (node (ref "R23") (pin "1") (pinfunction "1_1") (pintype "input"))
      (node (ref "R25") (pin "2") (pinfunction "2_2") (pintype "input"))
      (node (ref "R4") (pin "2") (pinfunction "2_2") (pintype "input"))
      (node (ref "R67") (pin "1") (pinfunction "1_1") (pintype "input"))
      (node (ref "R74") (pin "2") (pinfunction "2_2") (pintype "input"))
      (node (ref "U1") (pin "4") (pinfunction "VCC+_4") (pintype "input"))
      (node (ref "U32") (pin "10") (pinfunction "NC_10") (pintype "input"))
      (node (ref "U32") (pin "16") (pinfunction "VDD_16") (pintype "input"))
      (node (ref "U8") (pin "16") (pinfunction "VDD_16") (pintype "input"))
    )
    (net (code "4") (name "-5V") (class "Default")
      (node (ref "C19") (pin "1") (pinfunction "1_1") (pintype "input"))
      (node (ref "C20") (pin "2") (pinfunction "2_2") (pintype "input"))
      (node (ref "C22") (pin "2") (pinfunction "2_2") (pintype "input"))
      (node (ref "C39") (pin "2") (pinfunction "2_2") (pintype "input"))
      (node (ref "D6") (pin "1") (pinfunction "A_1") (pintype "input"))
      (node (ref "D8") (pin "1") (pinfunction "A_1") (pintype "input"))
      (node (ref "R66") (pin "2") (pinfunction "2_2") (pintype "input"))
      (node (ref "U11") (pin "4") (pinfunction "VCC-_4") (pintype "input"))
      (node (ref "U2") (pin "11") (pinfunction "VCC-_11") (pintype "input"))
      (node (ref "U3") (pin "7") (pinfunction "VEE_7") (pintype "input"))
    )
    (net (code "5") (name "-5V-D") (class "Default")
      (node (ref "C1") (pin "2") (pinfunction "2_2") (pintype "input"))
      (node (ref "C37") (pin "1") (pinfunction "1_1") (pintype "input"))
      (node (ref "C38") (pin "2") (pinfunction "2_2") (pintype "input"))
      (node (ref "C47") (pin "1") (pinfunction "1_1") (pintype "input"))
      (node (ref "C9") (pin "1") (pinfunction "1_1") (pintype "input"))
      (node (ref "D1") (pin "2") (pinfunction "A_2") (pintype "input"))
      (node (ref "Q2") (pin "3") (pinfunction "C_3") (pintype "input"))
      (node (ref "R12") (pin "1") (pinfunction "1_1") (pintype "input"))
      (node (ref "R24") (pin "1") (pinfunction "1_1") (pintype "input"))
      (node (ref "R66") (pin "1") (pinfunction "1_1") (pintype "input"))
      (node (ref "R76") (pin "2") (pinfunction "2_2") (pintype "input"))
      (node (ref "U1") (pin "11") (pinfunction "VCC-_11") (pintype "input"))
      (node (ref "U34") (pin "4") (pinfunction "GND_4") (pintype "input"))
      (node (ref "U8") (pin "7") (pinfunction "VEE_7") (pintype "input"))
    )
    (net (code "6") (name "/PA0_ADC") (class "Default")
      (node (ref "R62") (pin "2") (pinfunction "2_2") (pintype "input"))
      (node (ref "U6") (pin "6") (pinfunction "PA0_6") (pintype "bidirectional"))
    )
    (net (code "7") (name "/PA1_4053_11_SA_10X") (class "Default")
      (node (ref "U3") (pin "11") (pinfunction "SA_11") (pintype "input"))
      (node (ref "U6") (pin "7") (pinfunction "PA1_7") (pintype "bidirectional"))
    )
    (net (code "8") (name "/PA2_4053_10_SB_10X") (class "Default")
      (node (ref "U3") (pin "10") (pinfunction "SB_10") (pintype "input"))
      (node (ref "U6") (pin "8") (pinfunction "PA2_8") (pintype "bidirectional"))
    )
    (net (code "9") (name "/PA3_4053_9_SC_10X") (class "Default")
      (node (ref "U3") (pin "9") (pinfunction "SC_9") (pintype "input"))
      (node (ref "U6") (pin "9") (pinfunction "PA3_9") (pintype "bidirectional"))
    )
    (net (code "10") (name "/PA4_SPI1_NSS_HC595_12_RCK") (class "Default")
      (node (ref "R4") (pin "1") (pinfunction "1_1") (pintype "input"))
      (node (ref "U32") (pin "12") (pinfunction "RCK_12") (pintype "input"))
      (node (ref "U6") (pin "10") (pinfunction "PA4_10") (pintype "bidirectional"))
    )
    (net (code "11") (name "/PA5_SPI1_SCK_HC595_11_SCK") (class "Default")
      (node (ref "R25") (pin "1") (pinfunction "1_1") (pintype "input"))
      (node (ref "U32") (pin "11") (pinfunction "SCK_11") (pintype "input"))
      (node (ref "U6") (pin "11") (pinfunction "PA5_11") (pintype "bidirectional"))
    )
    (net (code "12") (name "/PA7_SPI1_MOSI_HC595_14_SER") (class "Default")
      (node (ref "R14") (pin "1") (pinfunction "1_1") (pintype "input"))
      (node (ref "U32") (pin "14") (pinfunction "SER_14") (pintype "input"))
      (node (ref "U6") (pin "13") (pinfunction "PA7_13") (pintype "bidirectional"))
    )
    (net (code "13") (name "/PA10_TIM1_SPWM") (class "Default")
      (node (ref "R22") (pin "2") (pinfunction "2_2") (pintype "input"))
      (node (ref "U6") (pin "18") (pinfunction "PA10_18") (pintype "bidirectional"))
    )
    (net (code "14") (name "/PB1_4053_DANG_WEI") (class "Default")
      (node (ref "U6") (pin "14") (pinfunction "PB1_14") (pintype "bidirectional"))
      (node (ref "U8") (pin "10") (pinfunction "SB_10") (pintype "input"))
      (node (ref "U8") (pin "11") (pinfunction "SA_11") (pintype "input"))
      (node (ref "U8") (pin "9") (pinfunction "SC_9") (pintype "input"))
    )
    (net (code "15") (name "GND") (class "Default")
      (node (ref "C1") (pin "1") (pinfunction "1_1") (pintype "input"))
      (node (ref "C12") (pin "2") (pinfunction "2_2") (pintype "input"))
      (node (ref "C13") (pin "1") (pinfunction "1_1") (pintype "input"))
      (node (ref "C14") (pin "2") (pinfunction "2_2") (pintype "input"))
      (node (ref "C15") (pin "2") (pinfunction "2_2") (pintype "input"))
      (node (ref "C16") (pin "2") (pinfunction "2_2") (pintype "input"))
      (node (ref "C17") (pin "1") (pinfunction "1_1") (pintype "input"))
      (node (ref "C18") (pin "1") (pinfunction "1_1") (pintype "input"))
      (node (ref "C19") (pin "2") (pinfunction "2_2") (pintype "input"))
      (node (ref "C2") (pin "1") (pinfunction "1_1") (pintype "input"))
      (node (ref "C20") (pin "1") (pinfunction "1_1") (pintype "input"))
      (node (ref "C21") (pin "1") (pinfunction "1_1") (pintype "input"))
      (node (ref "C22") (pin "1") (pinfunction "1_1") (pintype "input"))
      (node (ref "C23") (pin "1") (pinfunction "1_1") (pintype "input"))
      (node (ref "C25") (pin "1") (pinfunction "1_1") (pintype "input"))
      (node (ref "C34") (pin "1") (pinfunction "1_1") (pintype "input"))
      (node (ref "C35") (pin "2") (pinfunction "2_2") (pintype "input"))
      (node (ref "C37") (pin "2") (pinfunction "2_2") (pintype "input"))
      (node (ref "C38") (pin "1") (pinfunction "1_1") (pintype "input"))
      (node (ref "C39") (pin "1") (pinfunction "1_1") (pintype "input"))
      (node (ref "C4") (pin "1") (pinfunction "1_1") (pintype "input"))
      (node (ref "C40") (pin "1") (pinfunction "1_1") (pintype "input"))
      (node (ref "C41") (pin "1") (pinfunction "1_1") (pintype "input"))
      (node (ref "C42") (pin "2") (pinfunction "2_2") (pintype "input"))
      (node (ref "C43") (pin "1") (pinfunction "1_1") (pintype "input"))
      (node (ref "C46") (pin "2") (pinfunction "2_2") (pintype "input"))
      (node (ref "C48") (pin "1") (pinfunction "1_1") (pintype "input"))
      (node (ref "C5") (pin "1") (pinfunction "1_1") (pintype "input"))
      (node (ref "C50") (pin "1") (pinfunction "1_1") (pintype "input"))
      (node (ref "C6") (pin "1") (pinfunction "1_1") (pintype "input"))
      (node (ref "C7") (pin "1") (pinfunction "1_1") (pintype "input"))
      (node (ref "C8") (pin "1") (pinfunction "1_1") (pintype "input"))
      (node (ref "C9") (pin "2") (pinfunction "2_2") (pintype "input"))
      (node (ref "D12") (pin "1") (pinfunction "1_1") (pintype "input"))
      (node (ref "H5") (pin "3") (pinfunction "3_3") (pintype "input"))
      (node (ref "L3") (pin "1") (pinfunction "1_1") (pintype "input"))
      (node (ref "LC") (pin "1") (pinfunction "1_1") (pintype "unspecified"))
      (node (ref "LCD1") (pin "1") (pinfunction "VSS_1") (pintype "input"))
      (node (ref "LCD1") (pin "5") (pinfunction "RW_5") (pintype "input"))
      (node (ref "LDO1") (pin "1") (pinfunction "GND_1") (pintype "input"))
      (node (ref "R1") (pin "1") (pinfunction "1_1") (pintype "input"))
      (node (ref "R15") (pin "1") (pinfunction "1_1") (pintype "input"))
      (node (ref "R18") (pin "1") (pinfunction "1_1") (pintype "input"))
      (node (ref "R2") (pin "1") (pinfunction "1_1") (pintype "input"))
      (node (ref "R28") (pin "1") (pinfunction "1_1") (pintype "input"))
      (node (ref "R29") (pin "1") (pinfunction "1_1") (pintype "input"))
      (node (ref "R33") (pin "2") (pinfunction "2_2") (pintype "input"))
      (node (ref "R35") (pin "2") (pinfunction "2_2") (pintype "input"))
      (node (ref "R39") (pin "1") (pinfunction "1_1") (pintype "input"))
      (node (ref "R41") (pin "1") (pinfunction "1_1") (pintype "input"))
      (node (ref "R45") (pin "1") (pinfunction "1_1") (pintype "input"))
      (node (ref "R48") (pin "1") (pinfunction "1_1") (pintype "input"))
      (node (ref "R51") (pin "1") (pinfunction "1_1") (pintype "input"))
      (node (ref "R56") (pin "1") (pinfunction "1_1") (pintype "input"))
      (node (ref "R58") (pin "1") (pinfunction "1_1") (pintype "input"))
      (node (ref "R61") (pin "1") (pinfunction "1_1") (pintype "input"))
      (node (ref "R63") (pin "1") (pinfunction "1_1") (pintype "input"))
      (node (ref "R75") (pin "1") (pinfunction "1_1") (pintype "input"))
      (node (ref "R77") (pin "1") (pinfunction "1_1") (pintype "input"))
      (node (ref "R78") (pin "1") (pinfunction "1_1") (pintype "input"))
      (node (ref "R79") (pin "1") (pinfunction "1_1") (pintype "input"))
      (node (ref "R80") (pin "1") (pinfunction "1_1") (pintype "input"))
      (node (ref "R83") (pin "2") (pinfunction "2_2") (pintype "input"))
      (node (ref "SW1") (pin "3") (pinfunction "3_3") (pintype "input"))
      (node (ref "SW1") (pin "4") (pinfunction "4_4") (pintype "input"))
      (node (ref "SW2") (pin "3") (pinfunction "3_3") (pintype "input"))
      (node (ref "SW2") (pin "4") (pinfunction "4_4") (pintype "input"))
      (node (ref "U3") (pin "6") (pinfunction "E#_6") (pintype "input"))
      (node (ref "U3") (pin "8") (pinfunction "VSS_8") (pintype "input"))
      (node (ref "U32") (pin "13") (pinfunction "NC_13") (pintype "input"))
      (node (ref "U32") (pin "8") (pinfunction "GND_8") (pintype "input"))
      (node (ref "U33") (pin "2") (pinfunction "SE_2") (pintype "input"))
      (node (ref "U33") (pin "4") (pinfunction "GND_4") (pintype "input"))
      (node (ref "U35") (pin "1") (pinfunction "TEMP_1") (pintype "input"))
      (node (ref "U35") (pin "3") (pinfunction "GND_3") (pintype "input"))
      (node (ref "U37") (pin "2") (pinfunction "S_2") (pintype "input"))
      (node (ref "U6") (pin "15") (pinfunction "VSS_15") (pintype "input"))
      (node (ref "U8") (pin "6") (pinfunction "E#_6") (pintype "input"))
      (node (ref "U8") (pin "8") (pinfunction "VSS_8") (pintype "input"))
      (node (ref "USB1") (pin "1") (pinfunction "GND_1") (pintype "input"))
      (node (ref "USB1") (pin "12") (pinfunction "GND_12") (pintype "input"))
      (node (ref "USB1") (pin "13") (pinfunction "SHELL_13") (pintype "input"))
      (node (ref "USB1") (pin "14") (pinfunction "SHELL_14") (pintype "input"))
    )
    (net (code "16") (name "Net-(C3-Pad2)") (class "Default")
      (node (ref "C3") (pin "2") (pinfunction "2_2") (pintype "input"))
      (node (ref "C7") (pin "2") (pinfunction "2_2") (pintype "input"))
      (node (ref "R19") (pin "1") (pinfunction "1_1") (pintype "input"))
    )
    (net (code "17") (name "Net-(C4-Pad2)") (class "Default")
      (node (ref "C4") (pin "2") (pinfunction "2_2") (pintype "input"))
      (node (ref "R21") (pin "2") (pinfunction "2_2") (pintype "input"))
      (node (ref "R22") (pin "1") (pinfunction "1_1") (pintype "input"))
    )
    (net (code "18") (name "Net-(C5-Pad2)") (class "Default")
      (node (ref "C5") (pin "2") (pinfunction "2_2") (pintype "input"))
      (node (ref "R20") (pin "2") (pinfunction "2_2") (pintype "input"))
      (node (ref "R21") (pin "1") (pinfunction "1_1") (pintype "input"))
    )
    (net (code "19") (name "Net-(C6-Pad2)") (class "Default")
      (node (ref "C6") (pin "2") (pinfunction "2_2") (pintype "input"))
      (node (ref "R19") (pin "2") (pinfunction "2_2") (pintype "input"))
      (node (ref "R20") (pin "1") (pinfunction "1_1") (pintype "input"))
    )
    (net (code "20") (name "Net-(C24-Pad1)") (class "Default")
      (node (ref "C24") (pin "1") (pinfunction "1_1") (pintype "input"))
      (node (ref "C25") (pin "2") (pinfunction "2_2") (pintype "input"))
      (node (ref "R54") (pin "2") (pinfunction "2_2") (pintype "input"))
      (node (ref "R55") (pin "1") (pinfunction "1_1") (pintype "input"))
      (node (ref "R56") (pin "2") (pinfunction "2_2") (pintype "input"))
      (node (ref "R57") (pin "2") (pinfunction "2_2") (pintype "input"))
    )
    (net (code "21") (name "Net-(C44-Pad1)") (class "Default")
      (node (ref "C44") (pin "1") (pinfunction "1_1") (pintype "input"))
      (node (ref "R28") (pin "2") (pinfunction "2_2") (pintype "input"))
      (node (ref "R31") (pin "1") (pinfunction "1_1") (pintype "input"))
    )
    (net (code "22") (name "Net-(C44-Pad2)") (class "Default")
      (node (ref "C44") (pin "2") (pinfunction "2_2") (pintype "input"))
      (node (ref "LP") (pin "1") (pinfunction "1_1") (pintype "unspecified"))
    )
    (net (code "23") (name "Net-(C45-Pad1)") (class "Default")
      (node (ref "C45") (pin "1") (pinfunction "1_1") (pintype "input"))
      (node (ref "R29") (pin "2") (pinfunction "2_2") (pintype "input"))
      (node (ref "R30") (pin "1") (pinfunction "1_1") (pintype "input"))
    )
    (net (code "24") (name "Net-(C45-Pad2)") (class "Default")
      (node (ref "C45") (pin "2") (pinfunction "2_2") (pintype "input"))
      (node (ref "HP") (pin "1") (pinfunction "1_1") (pintype "unspecified"))
    )
    (net (code "25") (name "Net-(D1-K)") (class "Default")
      (node (ref "D1") (pin "1") (pinfunction "K_1") (pintype "input"))
      (node (ref "L3") (pin "2") (pinfunction "2_2") (pintype "input"))
      (node (ref "U34") (pin "2") (pinfunction "SE_2") (pintype "input"))
    )
    (net (code "26") (name "Net-(D2-A)") (class "Default")
      (node (ref "D2") (pin "1") (pinfunction "A_1") (pintype "input"))
      (node (ref "Q4") (pin "1") (pinfunction "B_1") (pintype "input"))
      (node (ref "R11") (pin "1") (pinfunction "1_1") (pintype "input"))
    )
    (net (code "27") (name "Net-(D2-C)") (class "Default")
      (node (ref "D2") (pin "2") (pinfunction "C_2") (pintype "input"))
      (node (ref "D3") (pin "1") (pinfunction "A_1") (pintype "input"))
      (node (ref "U1") (pin "7") (pinfunction "OUT2_7") (pintype "input"))
    )
    (net (code "28") (name "Net-(D3-C)") (class "Default")
      (node (ref "D3") (pin "2") (pinfunction "C_2") (pintype "input"))
      (node (ref "Q2") (pin "1") (pinfunction "B_1") (pintype "input"))
      (node (ref "R12") (pin "2") (pinfunction "2_2") (pintype "input"))
    )
    (net (code "29") (name "Net-(D4-A)") (class "Default")
      (node (ref "C10") (pin "2") (pinfunction "2_2") (pintype "input"))
      (node (ref "C11") (pin "2") (pinfunction "2_2") (pintype "input"))
      (node (ref "D4") (pin "2") (pinfunction "A_2") (pintype "input"))
      (node (ref "D5") (pin "2") (pinfunction "A_2") (pintype "input"))
    )
    (net (code "30") (name "Net-(D4-K)") (class "Default")
      (node (ref "C10") (pin "1") (pinfunction "1_1") (pintype "input"))
      (node (ref "D12") (pin "2") (pinfunction "2_2") (pintype "input"))
      (node (ref "D4") (pin "1") (pinfunction "K_1") (pintype "input"))
      (node (ref "Q7") (pin "2") (pinfunction "S_2") (pintype "input"))
      (node (ref "R6") (pin "1") (pinfunction "1_1") (pintype "input"))
      (node (ref "R71") (pin "1") (pinfunction "1_1") (pintype "input"))
    )
    (net (code "31") (name "Net-(D5-K)") (class "Default")
      (node (ref "C11") (pin "1") (pinfunction "1_1") (pintype "input"))
      (node (ref "D5") (pin "1") (pinfunction "K_1") (pintype "input"))
      (node (ref "HC") (pin "1") (pinfunction "1_1") (pintype "unspecified"))
    )
    (net (code "32") (name "Net-(D6-C)") (class "Default")
      (node (ref "D6") (pin "2") (pinfunction "C_2") (pintype "input"))
      (node (ref "D7") (pin "1") (pinfunction "A_1") (pintype "input"))
      (node (ref "R30") (pin "2") (pinfunction "2_2") (pintype "input"))
      (node (ref "U2") (pin "3") (pinfunction "POS1_3") (pintype "input"))
    )
    (net (code "33") (name "Net-(D8-C)") (class "Default")
      (node (ref "D8") (pin "2") (pinfunction "C_2") (pintype "input"))
      (node (ref "D9") (pin "1") (pinfunction "A_1") (pintype "input"))
      (node (ref "R31") (pin "2") (pinfunction "2_2") (pintype "input"))
      (node (ref "U2") (pin "12") (pinfunction "POS4_12") (pintype "input"))
    )
    (net (code "34") (name "Net-(D13-A)") (class "Default")
      (node (ref "D13") (pin "2") (pinfunction "A_2") (pintype "input"))
      (node (ref "L2") (pin "2") (pinfunction "2_2") (pintype "input"))
      (node (ref "U33") (pin "1") (pinfunction "SC_1") (pintype "input"))
    )
    (net (code "35") (name "Net-(LCD1-DB4)") (class "Default")
      (node (ref "LCD1") (pin "11") (pinfunction "DB4_11") (pintype "input"))
      (node (ref "U32") (pin "2") (pinfunction "Q2_2") (pintype "input"))
    )
    (net (code "36") (name "Net-(LCD1-DB5)") (class "Default")
      (node (ref "LCD1") (pin "12") (pinfunction "DB5_12") (pintype "input"))
      (node (ref "U32") (pin "3") (pinfunction "Q3_3") (pintype "input"))
    )
    (net (code "37") (name "Net-(LCD1-DB6)") (class "Default")
      (node (ref "LCD1") (pin "13") (pinfunction "DB6_13") (pintype "input"))
      (node (ref "U32") (pin "4") (pinfunction "Q4_4") (pintype "input"))
    )
    (net (code "38") (name "Net-(LCD1-DB7)") (class "Default")
      (node (ref "LCD1") (pin "14") (pinfunction "DB7_14") (pintype "input"))
      (node (ref "U32") (pin "5") (pinfunction "Q5_5") (pintype "input"))
    )
    (net (code "39") (name "Net-(LCD1-E)") (class "Default")
      (node (ref "LCD1") (pin "6") (pinfunction "E_6") (pintype "input"))
      (node (ref "U32") (pin "1") (pinfunction "Q1_1") (pintype "input"))
    )
    (net (code "40") (name "Net-(LCD1-K)") (class "Default")
      (node (ref "LCD1") (pin "16") (pinfunction "K_16") (pintype "input"))
      (node (ref "R33") (pin "1") (pinfunction "1_1") (pintype "input"))
    )
    (net (code "41") (name "Net-(LCD1-RS)") (class "Default")
      (node (ref "LCD1") (pin "4") (pinfunction "RS_4") (pintype "input"))
      (node (ref "U32") (pin "15") (pinfunction "Q0_15") (pintype "input"))
    )
    (net (code "42") (name "Net-(LCD1-V0)") (class "Default")
      (node (ref "LCD1") (pin "3") (pinfunction "V0_3") (pintype "input"))
      (node (ref "R34") (pin "2") (pinfunction "2_2") (pintype "input"))
    )
    (net (code "43") (name "Net-(LDO1-VDD)") (class "Default")
      (node (ref "C12") (pin "1") (pinfunction "1_1") (pintype "input"))
      (node (ref "C48") (pin "2") (pinfunction "2_2") (pintype "input"))
      (node (ref "LDO1") (pin "3") (pinfunction "VDD_3") (pintype "input"))
      (node (ref "R26") (pin "2") (pinfunction "2_2") (pintype "input"))
      (node (ref "R72") (pin "2") (pinfunction "2_2") (pintype "input"))
      (node (ref "SW3") (pin "2") (pinfunction "2_2") (pintype "input"))
      (node (ref "SW3") (pin "3") (pinfunction "3_3") (pintype "input"))
      (node (ref "U33") (pin "6") (pinfunction "VCC_6") (pintype "input"))
      (node (ref "U34") (pin "6") (pinfunction "VCC_6") (pintype "input"))
    )
    (net (code "44") (name "Net-(LED1-A)") (class "Default")
      (node (ref "LED1") (pin "2") (pinfunction "A_2") (pintype "input"))
      (node (ref "R81") (pin "2") (pinfunction "2_2") (pintype "input"))
    )
    (net (code "45") (name "Net-(LED1-C)") (class "Default")
      (node (ref "C50") (pin "2") (pinfunction "2_2") (pintype "input"))
      (node (ref "LED1") (pin "1") (pinfunction "C_1") (pintype "input"))
      (node (ref "LED2") (pin "1") (pinfunction "C_1") (pintype "input"))
      (node (ref "U35") (pin "4") (pinfunction "Vcc_4") (pintype "input"))
      (node (ref "U35") (pin "8") (pinfunction "CE_8") (pintype "input"))
      (node (ref "USB1") (pin "11") (pinfunction "VBUS_11") (pintype "input"))
      (node (ref "USB1") (pin "2") (pinfunction "VBUS_2") (pintype "input"))
    )
    (net (code "46") (name "Net-(LED2-A)") (class "Default")
      (node (ref "LED2") (pin "2") (pinfunction "A_2") (pintype "input"))
      (node (ref "R82") (pin "2") (pinfunction "2_2") (pintype "input"))
    )
    (net (code "47") (name "Net-(Q2-E)") (class "Default")
      (node (ref "Q2") (pin "2") (pinfunction "E_2") (pintype "input"))
      (node (ref "R9") (pin "1") (pinfunction "1_1") (pintype "input"))
    )
    (net (code "48") (name "Net-(Q4-E)") (class "Default")
      (node (ref "Q4") (pin "2") (pinfunction "E_2") (pintype "input"))
      (node (ref "R10") (pin "2") (pinfunction "2_2") (pintype "input"))
    )
    (net (code "49") (name "Net-(Q6-D)") (class "Default")
      (node (ref "Q6") (pin "3") (pinfunction "D_3") (pintype "input"))
      (node (ref "Q7") (pin "3") (pinfunction "D_3") (pintype "input"))
    )
    (net (code "50") (name "Net-(Q6-G)") (class "Default")
      (node (ref "Q6") (pin "1") (pinfunction "G_1") (pintype "input"))
      (node (ref "Q7") (pin "1") (pinfunction "G_1") (pintype "input"))
      (node (ref "U8") (pin "14") (pinfunction "ZA_14") (pintype "input"))
    )
    (net (code "51") (name "Net-(Q6-S)") (class "Default")
      (node (ref "Q6") (pin "2") (pinfunction "S_2") (pintype "input"))
      (node (ref "R5") (pin "1") (pinfunction "1_1") (pintype "input"))
      (node (ref "R69") (pin "1") (pinfunction "1_1") (pintype "input"))
      (node (ref "R71") (pin "2") (pinfunction "2_2") (pintype "input"))
    )
    (net (code "52") (name "Net-(R1-Pad2)") (class "Default")
      (node (ref "R1") (pin "2") (pinfunction "2_2") (pintype "input"))
      (node (ref "R2") (pin "2") (pinfunction "2_2") (pintype "input"))
      (node (ref "R34") (pin "1") (pinfunction "1_1") (pintype "input"))
    )
    (net (code "53") (name "Net-(R10-Pad1)") (class "Default")
      (node (ref "R10") (pin "1") (pinfunction "1_1") (pintype "input"))
      (node (ref "R3") (pin "1") (pinfunction "1_1") (pintype "input"))
      (node (ref "R69") (pin "2") (pinfunction "2_2") (pintype "input"))
      (node (ref "R9") (pin "2") (pinfunction "2_2") (pintype "input"))
    )
    (net (code "54") (name "Net-(U1-NEG1)") (class "Default")
      (node (ref "R13") (pin "2") (pinfunction "2_2") (pintype "input"))
      (node (ref "U1") (pin "1") (pinfunction "OUT1_1") (pintype "input"))
      (node (ref "U1") (pin "2") (pinfunction "NEG1_2") (pintype "input"))
    )
    (net (code "55") (name "Net-(U1-NEG2)") (class "Default")
      (node (ref "R13") (pin "1") (pinfunction "1_1") (pintype "input"))
      (node (ref "R17") (pin "2") (pinfunction "2_2") (pintype "input"))
      (node (ref "U1") (pin "6") (pinfunction "NEG2_6") (pintype "input"))
    )
    (net (code "56") (name "Net-(U1-NEG3)") (class "Default")
      (node (ref "R17") (pin "1") (pinfunction "1_1") (pintype "input"))
      (node (ref "U1") (pin "8") (pinfunction "OUT3_8") (pintype "input"))
      (node (ref "U1") (pin "9") (pinfunction "NEG3_9") (pintype "input"))
    )
    (net (code "57") (name "Net-(U1-NEG4)") (class "Default")
      (node (ref "R16") (pin "2") (pinfunction "2_2") (pintype "input"))
      (node (ref "U1") (pin "13") (pinfunction "NEG4_13") (pintype "input"))
      (node (ref "U1") (pin "14") (pinfunction "OUT4_14") (pintype "input"))
    )
    (net (code "58") (name "Net-(U1-POS1)") (class "Default")
      (node (ref "U1") (pin "3") (pinfunction "POS1_3") (pintype "input"))
      (node (ref "U8") (pin "4") (pinfunction "ZC_4") (pintype "input"))
    )
    (net (code "59") (name "Net-(U1-POS2)") (class "Default")
      (node (ref "R15") (pin "2") (pinfunction "2_2") (pintype "input"))
      (node (ref "R16") (pin "1") (pinfunction "1_1") (pintype "input"))
      (node (ref "U1") (pin "5") (pinfunction "POS2_5") (pintype "input"))
    )
    (net (code "60") (name "Net-(U1-POS3)") (class "Default")
      (node (ref "C3") (pin "1") (pinfunction "1_1") (pintype "input"))
      (node (ref "R18") (pin "2") (pinfunction "2_2") (pintype "input"))
      (node (ref "U1") (pin "10") (pinfunction "POS3_10") (pintype "input"))
    )
    (net (code "61") (name "Net-(U1-POS4)") (class "Default")
      (node (ref "U1") (pin "12") (pinfunction "POS4_12") (pintype "input"))
      (node (ref "U8") (pin "15") (pinfunction "ZB_15") (pintype "input"))
    )
    (net (code "62") (name "Net-(U2-NEG1)") (class "Default")
      (node (ref "R42") (pin "1") (pinfunction "1_1") (pintype "input"))
      (node (ref "U2") (pin "1") (pinfunction "OUT1_1") (pintype "input"))
      (node (ref "U2") (pin "2") (pinfunction "NEG1_2") (pintype "input"))
    )
    (net (code "63") (name "Net-(U2-NEG2)") (class "Default")
      (node (ref "C30") (pin "1") (pinfunction "1_1") (pintype "input"))
      (node (ref "R36") (pin "2") (pinfunction "2_2") (pintype "input"))
      (node (ref "R38") (pin "1") (pinfunction "1_1") (pintype "input"))
      (node (ref "R39") (pin "2") (pinfunction "2_2") (pintype "input"))
      (node (ref "U2") (pin "6") (pinfunction "NEG2_6") (pintype "input"))
    )
    (net (code "64") (name "Net-(U2-NEG3)") (class "Default")
      (node (ref "R37") (pin "1") (pinfunction "1_1") (pintype "input"))
      (node (ref "R42") (pin "2") (pinfunction "2_2") (pintype "input"))
      (node (ref "U2") (pin "9") (pinfunction "NEG3_9") (pintype "input"))
    )
    (net (code "65") (name "Net-(U2-NEG4)") (class "Default")
      (node (ref "R40") (pin "2") (pinfunction "2_2") (pintype "input"))
      (node (ref "U2") (pin "13") (pinfunction "NEG4_13") (pintype "input"))
      (node (ref "U2") (pin "14") (pinfunction "OUT4_14") (pintype "input"))
    )
    (net (code "66") (name "Net-(U2-OUT2)") (class "Default")
      (node (ref "C30") (pin "2") (pinfunction "2_2") (pintype "input"))
      (node (ref "R36") (pin "1") (pinfunction "1_1") (pintype "input"))
      (node (ref "R38") (pin "2") (pinfunction "2_2") (pintype "input"))
      (node (ref "R43") (pin "2") (pinfunction "2_2") (pintype "input"))
      (node (ref "R44") (pin "2") (pinfunction "2_2") (pintype "input"))
      (node (ref "U2") (pin "7") (pinfunction "OUT2_7") (pintype "input"))
      (node (ref "U3") (pin "1") (pinfunction "Y1B_1") (pintype "input"))
    )
    (net (code "67") (name "Net-(U2-OUT3)") (class "Default")
      (node (ref "R37") (pin "2") (pinfunction "2_2") (pintype "input"))
      (node (ref "R46") (pin "2") (pinfunction "2_2") (pintype "input"))
      (node (ref "R47") (pin "2") (pinfunction "2_2") (pintype "input"))
      (node (ref "U2") (pin "8") (pinfunction "OUT3_8") (pintype "input"))
      (node (ref "U3") (pin "3") (pinfunction "Y1C_3") (pintype "input"))
    )
    (net (code "68") (name "Net-(U2-POS2)") (class "Default")
      (node (ref "C31") (pin "2") (pinfunction "2_2") (pintype "input"))
      (node (ref "R63") (pin "2") (pinfunction "2_2") (pintype "input"))
      (node (ref "U2") (pin "5") (pinfunction "POS2_5") (pintype "input"))
    )
    (net (code "69") (name "Net-(U2-POS3)") (class "Default")
      (node (ref "R40") (pin "1") (pinfunction "1_1") (pintype "input"))
      (node (ref "R41") (pin "2") (pinfunction "2_2") (pintype "input"))
      (node (ref "U2") (pin "10") (pinfunction "POS3_10") (pintype "input"))
    )
    (net (code "70") (name "Net-(U3-Y0A)") (class "Default")
      (node (ref "R49") (pin "1") (pinfunction "1_1") (pintype "input"))
      (node (ref "R50") (pin "1") (pinfunction "1_1") (pintype "input"))
      (node (ref "R51") (pin "2") (pinfunction "2_2") (pintype "input"))
      (node (ref "U3") (pin "12") (pinfunction "Y0A_12") (pintype "input"))
    )
    (net (code "71") (name "Net-(U3-Y0B)") (class "Default")
      (node (ref "R43") (pin "1") (pinfunction "1_1") (pintype "input"))
      (node (ref "R44") (pin "1") (pinfunction "1_1") (pintype "input"))
      (node (ref "R45") (pin "2") (pinfunction "2_2") (pintype "input"))
      (node (ref "U3") (pin "2") (pinfunction "Y0B_2") (pintype "input"))
    )
    (net (code "72") (name "Net-(U3-Y0C)") (class "Default")
      (node (ref "R46") (pin "1") (pinfunction "1_1") (pintype "input"))
      (node (ref "R47") (pin "1") (pinfunction "1_1") (pintype "input"))
      (node (ref "R48") (pin "2") (pinfunction "2_2") (pintype "input"))
      (node (ref "U3") (pin "5") (pinfunction "Y0C_5") (pintype "input"))
    )
    (net (code "73") (name "Net-(U3-ZA)") (class "Default")
      (node (ref "C26") (pin "1") (pinfunction "1_1") (pintype "input"))
      (node (ref "U3") (pin "14") (pinfunction "ZA_14") (pintype "input"))
    )
    (net (code "74") (name "Net-(U3-ZB)") (class "Default")
      (node (ref "C27") (pin "1") (pinfunction "1_1") (pintype "input"))
      (node (ref "U3") (pin "15") (pinfunction "ZB_15") (pintype "input"))
    )
    (net (code "75") (name "Net-(U3-ZC)") (class "Default")
      (node (ref "C31") (pin "1") (pinfunction "1_1") (pintype "input"))
      (node (ref "U3") (pin "4") (pinfunction "ZC_4") (pintype "input"))
    )
    (net (code "76") (name "Net-(U6-BOOT0)") (class "Default")
      (node (ref "R35") (pin "1") (pinfunction "1_1") (pintype "input"))
      (node (ref "U6") (pin "1") (pinfunction "BOOT0_1") (pintype "input"))
    )
    (net (code "77") (name "Net-(U6-NRST)") (class "Default")
      (node (ref "C14") (pin "1") (pinfunction "1_1") (pintype "input"))
      (node (ref "U6") (pin "4") (pinfunction "NRST_4") (pintype "bidirectional"))
    )
    (net (code "78") (name "Net-(U6-PA6)") (class "Default")
      (node (ref "SW1") (pin "1") (pinfunction "1_1") (pintype "input"))
      (node (ref "SW1") (pin "2") (pinfunction "2_2") (pintype "input"))
      (node (ref "U6") (pin "12") (pinfunction "PA6_12") (pintype "bidirectional"))
    )
    (net (code "79") (name "Net-(U6-PA9)") (class "Default")
      (node (ref "SW2") (pin "1") (pinfunction "1_1") (pintype "input"))
      (node (ref "SW2") (pin "2") (pinfunction "2_2") (pintype "input"))
      (node (ref "U6") (pin "17") (pinfunction "PA9_17") (pintype "bidirectional"))
    )
    (net (code "80") (name "Net-(U6-PA13(SWDIO))") (class "Default")
      (node (ref "H5") (pin "2") (pinfunction "2_2") (pintype "input"))
      (node (ref "U6") (pin "19") (pinfunction "PA13(SWDIO)_19") (pintype "bidirectional"))
    )
    (net (code "81") (name "Net-(U6-PA14(SWCLK))") (class "Default")
      (node (ref "H5") (pin "1") (pinfunction "1_1") (pintype "input"))
      (node (ref "U6") (pin "20") (pinfunction "PA14(SWCLK)_20") (pintype "bidirectional"))
    )
    (net (code "82") (name "Net-(U6-PF0-OSC_IN(PF0))") (class "Default")
      (node (ref "C15") (pin "1") (pinfunction "1_1") (pintype "input"))
      (node (ref "U6") (pin "2") (pinfunction "PF0-OSC_IN(PF0)_2") (pintype "bidirectional"))
      (node (ref "X1") (pin "1") (pinfunction "OSC1_1") (pintype "input"))
    )
    (net (code "83") (name "Net-(U6-PF1-OSC_OUT(PF1))") (class "Default")
      (node (ref "C16") (pin "1") (pinfunction "1_1") (pintype "input"))
      (node (ref "U6") (pin "3") (pinfunction "PF1-OSC_OUT(PF1)_3") (pintype "bidirectional"))
      (node (ref "X1") (pin "2") (pinfunction "OSC2_2") (pintype "input"))
    )
    (net (code "84") (name "Net-(U6-VDDA)") (class "Default")
      (node (ref "C17") (pin "2") (pinfunction "2_2") (pintype "input"))
      (node (ref "L1") (pin "1") (pinfunction "1_1") (pintype "input"))
      (node (ref "U6") (pin "5") (pinfunction "VDDA_5") (pintype "input"))
    )
    (net (code "85") (name "Net-(U8-Y0A)") (class "Default")
      (node (ref "R23") (pin "2") (pinfunction "2_2") (pintype "input"))
      (node (ref "U8") (pin "12") (pinfunction "Y0A_12") (pintype "input"))
    )
    (net (code "86") (name "Net-(U8-Y0B)") (class "Default")
      (node (ref "R5") (pin "2") (pinfunction "2_2") (pintype "input"))
      (node (ref "U8") (pin "2") (pinfunction "Y0B_2") (pintype "input"))
      (node (ref "U8") (pin "3") (pinfunction "Y1C_3") (pintype "input"))
    )
    (net (code "87") (name "Net-(U8-Y0C)") (class "Default")
      (node (ref "R3") (pin "2") (pinfunction "2_2") (pintype "input"))
      (node (ref "U8") (pin "5") (pinfunction "Y0C_5") (pintype "input"))
    )
    (net (code "88") (name "Net-(U8-Y1A)") (class "Default")
      (node (ref "R24") (pin "2") (pinfunction "2_2") (pintype "input"))
      (node (ref "U8") (pin "13") (pinfunction "Y1A_13") (pintype "input"))
    )
    (net (code "89") (name "Net-(U8-Y1B)") (class "Default")
      (node (ref "R6") (pin "2") (pinfunction "2_2") (pintype "input"))
      (node (ref "U8") (pin "1") (pinfunction "Y1B_1") (pintype "input"))
    )
    (net (code "90") (name "Net-(U11A-IN1+)") (class "Default")
      (node (ref "C26") (pin "2") (pinfunction "2_2") (pintype "input"))
      (node (ref "R57") (pin "1") (pinfunction "1_1") (pintype "input"))
      (node (ref "U11") (pin "3") (pinfunction "IN1+_3") (pintype "input"))
    )
    (net (code "91") (name "Net-(U11A-IN1-)") (class "Default")
      (node (ref "C28") (pin "1") (pinfunction "1_1") (pintype "input"))
      (node (ref "R52") (pin "1") (pinfunction "1_1") (pintype "input"))
      (node (ref "R53") (pin "2") (pinfunction "2_2") (pintype "input"))
      (node (ref "R54") (pin "1") (pinfunction "1_1") (pintype "input"))
      (node (ref "U11") (pin "2") (pinfunction "IN1-_2") (pintype "input"))
    )
    (net (code "92") (name "Net-(U11A-OUT1)") (class "Default")
      (node (ref "C28") (pin "2") (pinfunction "2_2") (pintype "input"))
      (node (ref "R52") (pin "2") (pinfunction "2_2") (pintype "input"))
      (node (ref "R53") (pin "1") (pinfunction "1_1") (pintype "input"))
      (node (ref "R62") (pin "1") (pinfunction "1_1") (pintype "input"))
      (node (ref "U11") (pin "1") (pinfunction "OUT1_1") (pintype "output"))
    )
    (net (code "93") (name "Net-(U11B-IN2+)") (class "Default")
      (node (ref "C27") (pin "2") (pinfunction "2_2") (pintype "input"))
      (node (ref "R58") (pin "2") (pinfunction "2_2") (pintype "input"))
      (node (ref "U11") (pin "5") (pinfunction "IN2+_5") (pintype "input"))
    )
    (net (code "94") (name "Net-(U11B-IN2-)") (class "Default")
      (node (ref "C29") (pin "1") (pinfunction "1_1") (pintype "input"))
      (node (ref "R59") (pin "1") (pinfunction "1_1") (pintype "input"))
      (node (ref "R60") (pin "2") (pinfunction "2_2") (pintype "input"))
      (node (ref "R61") (pin "2") (pinfunction "2_2") (pintype "input"))
      (node (ref "U11") (pin "6") (pinfunction "IN2-_6") (pintype "input"))
    )
    (net (code "95") (name "Net-(U11B-OUT2)") (class "Default")
      (node (ref "C29") (pin "2") (pinfunction "2_2") (pintype "input"))
      (node (ref "R49") (pin "2") (pinfunction "2_2") (pintype "input"))
      (node (ref "R50") (pin "2") (pinfunction "2_2") (pintype "input"))
      (node (ref "R59") (pin "2") (pinfunction "2_2") (pintype "input"))
      (node (ref "R60") (pin "1") (pinfunction "1_1") (pintype "input"))
      (node (ref "U11") (pin "7") (pinfunction "OUT2_7") (pintype "output"))
      (node (ref "U3") (pin "13") (pinfunction "Y1A_13") (pintype "input"))
    )
    (net (code "96") (name "Net-(U33-CT)") (class "Default")
      (node (ref "C46") (pin "1") (pinfunction "1_1") (pintype "input"))
      (node (ref "U33") (pin "3") (pinfunction "CT_3") (pintype "input"))
    )
    (net (code "97") (name "Net-(U33-DC)") (class "Default")
      (node (ref "R73") (pin "1") (pinfunction "1_1") (pintype "input"))
      (node (ref "U33") (pin "8") (pinfunction "DC_8") (pintype "input"))
    )
    (net (code "98") (name "Net-(U33-FB)") (class "Default")
      (node (ref "R74") (pin "1") (pinfunction "1_1") (pintype "input"))
      (node (ref "R75") (pin "2") (pinfunction "2_2") (pintype "input"))
      (node (ref "U33") (pin "5") (pinfunction "FB_5") (pintype "input"))
    )
    (net (code "99") (name "Net-(U33-IPK)") (class "Default")
      (node (ref "L2") (pin "1") (pinfunction "1_1") (pintype "input"))
      (node (ref "R72") (pin "1") (pinfunction "1_1") (pintype "input"))
      (node (ref "R73") (pin "2") (pinfunction "2_2") (pintype "input"))
      (node (ref "U33") (pin "7") (pinfunction "IPK_7") (pintype "input"))
    )
    (net (code "100") (name "Net-(U34-CT)") (class "Default")
      (node (ref "C47") (pin "2") (pinfunction "2_2") (pintype "input"))
      (node (ref "U34") (pin "3") (pinfunction "CT_3") (pintype "input"))
    )
    (net (code "101") (name "Net-(U34-DC)") (class "Default")
      (node (ref "R26") (pin "1") (pinfunction "1_1") (pintype "input"))
      (node (ref "U34") (pin "1") (pinfunction "SC_1") (pintype "input"))
      (node (ref "U34") (pin "7") (pinfunction "IPK_7") (pintype "input"))
      (node (ref "U34") (pin "8") (pinfunction "DC_8") (pintype "input"))
    )
    (net (code "102") (name "Net-(U34-FB)") (class "Default")
      (node (ref "R76") (pin "1") (pinfunction "1_1") (pintype "input"))
      (node (ref "R77") (pin "2") (pinfunction "2_2") (pintype "input"))
      (node (ref "U34") (pin "5") (pinfunction "FB_5") (pintype "input"))
    )
    (net (code "103") (name "Net-(U35-BAT)") (class "Default")
      (node (ref "C13") (pin "2") (pinfunction "2_2") (pintype "input"))
      (node (ref "H6") (pin "1") (pinfunction "1_1") (pintype "unspecified"))
      (node (ref "R84") (pin "1") (pinfunction "1_1") (pintype "input"))
      (node (ref "SW3") (pin "1") (pinfunction "1_1") (pintype "input"))
      (node (ref "U35") (pin "5") (pinfunction "BAT_5") (pintype "input"))
    )
    (net (code "104") (name "Net-(U35-CHRG#)") (class "Default")
      (node (ref "R81") (pin "1") (pinfunction "1_1") (pintype "input"))
      (node (ref "U35") (pin "7") (pinfunction "CHRG#_7") (pintype "input"))
    )
    (net (code "105") (name "Net-(U35-PROG)") (class "Default")
      (node (ref "R80") (pin "2") (pinfunction "2_2") (pintype "input"))
      (node (ref "U35") (pin "2") (pinfunction "PROG_2") (pintype "input"))
    )
    (net (code "106") (name "Net-(U35-STDBY#)") (class "Default")
      (node (ref "R82") (pin "1") (pinfunction "1_1") (pintype "input"))
      (node (ref "U35") (pin "6") (pinfunction "STDBY#_6") (pintype "input"))
    )
    (net (code "107") (name "Net-(U36-CS)") (class "Default")
      (node (ref "R83") (pin "1") (pinfunction "1_1") (pintype "input"))
      (node (ref "U36") (pin "2") (pinfunction "CS_2") (pintype "input"))
    )
    (net (code "108") (name "Net-(U36-GND)") (class "Default")
      (node (ref "C49") (pin "1") (pinfunction "1_1") (pintype "input"))
      (node (ref "H7") (pin "1") (pinfunction "1_1") (pintype "unspecified"))
      (node (ref "U36") (pin "6") (pinfunction "GND_6") (pintype "input"))
      (node (ref "U38") (pin "2") (pinfunction "S_2") (pintype "input"))
    )
    (net (code "109") (name "Net-(U36-OC)") (class "Default")
      (node (ref "U36") (pin "3") (pinfunction "OC_3") (pintype "input"))
      (node (ref "U37") (pin "1") (pinfunction "G_1") (pintype "input"))
    )
    (net (code "110") (name "Net-(U36-OD)") (class "Default")
      (node (ref "U36") (pin "1") (pinfunction "OD_1") (pintype "input"))
      (node (ref "U38") (pin "1") (pinfunction "G_1") (pintype "input"))
    )
    (net (code "111") (name "Net-(U36-VCC)") (class "Default")
      (node (ref "C49") (pin "2") (pinfunction "2_2") (pintype "input"))
      (node (ref "R84") (pin "2") (pinfunction "2_2") (pintype "input"))
      (node (ref "U36") (pin "5") (pinfunction "VCC_5") (pintype "input"))
    )
    (net (code "112") (name "Net-(U37-D)") (class "Default")
      (node (ref "U37") (pin "3") (pinfunction "D_3") (pintype "input"))
      (node (ref "U38") (pin "3") (pinfunction "D_3") (pintype "input"))
    )
    (net (code "113") (name "Net-(USB1-CC1)") (class "Default")
      (node (ref "R78") (pin "2") (pinfunction "2_2") (pintype "input"))
      (node (ref "USB1") (pin "4") (pinfunction "CC1_4") (pintype "input"))
    )
    (net (code "114") (name "Net-(USB1-CC2)") (class "Default")
      (node (ref "R79") (pin "2") (pinfunction "2_2") (pintype "input"))
      (node (ref "USB1") (pin "10") (pinfunction "CC2_10") (pintype "input"))
    )
    (net (code "115") (name "unconnected-(LCD1-DB0-Pad7)") (class "Default")
      (node (ref "LCD1") (pin "7") (pinfunction "DB0_7") (pintype "input+no_connect"))
    )
    (net (code "116") (name "unconnected-(LCD1-DB1-Pad8)") (class "Default")
      (node (ref "LCD1") (pin "8") (pinfunction "DB1_8") (pintype "input+no_connect"))
    )
    (net (code "117") (name "unconnected-(LCD1-DB2-Pad9)") (class "Default")
      (node (ref "LCD1") (pin "9") (pinfunction "DB2_9") (pintype "input+no_connect"))
    )
    (net (code "118") (name "unconnected-(LCD1-DB3-Pad10)") (class "Default")
      (node (ref "LCD1") (pin "10") (pinfunction "DB3_10") (pintype "input+no_connect"))
    )
    (net (code "119") (name "unconnected-(U32-Q6-Pad6)") (class "Default")
      (node (ref "U32") (pin "6") (pinfunction "Q6_6") (pintype "input"))
    )
    (net (code "120") (name "unconnected-(U32-Q7&apos;-Pad9)") (class "Default")
      (node (ref "U32") (pin "9") (pinfunction "Q7&apos;_9") (pintype "input"))
    )
    (net (code "121") (name "unconnected-(U32-Q7-Pad7)") (class "Default")
      (node (ref "U32") (pin "7") (pinfunction "Q7_7") (pintype "input"))
    )
    (net (code "122") (name "unconnected-(U36-TD-Pad4)") (class "Default")
      (node (ref "U36") (pin "4") (pinfunction "TD_4") (pintype "input+no_connect"))
    )
    (net (code "123") (name "unconnected-(USB1-DN1-Pad7)") (class "Default")
      (node (ref "USB1") (pin "7") (pinfunction "DN1_7") (pintype "input+no_connect"))
    )
    (net (code "124") (name "unconnected-(USB1-DN2-Pad5)") (class "Default")
      (node (ref "USB1") (pin "5") (pinfunction "DN2_5") (pintype "input+no_connect"))
    )
    (net (code "125") (name "unconnected-(USB1-DP1-Pad6)") (class "Default")
      (node (ref "USB1") (pin "6") (pinfunction "DP1_6") (pintype "input+no_connect"))
    )
    (net (code "126") (name "unconnected-(USB1-DP2-Pad8)") (class "Default")
      (node (ref "USB1") (pin "8") (pinfunction "DP2_8") (pintype "input+no_connect"))
    )
    (net (code "127") (name "unconnected-(USB1-SBU1-Pad9)") (class "Default")
      (node (ref "USB1") (pin "9") (pinfunction "SBU1_9") (pintype "input+no_connect"))
    )
    (net (code "128") (name "unconnected-(USB1-SBU2-Pad3)") (class "Default")
      (node (ref "USB1") (pin "3") (pinfunction "SBU2_3") (pintype "input+no_connect"))
    )
  )
)
